# AJH_module_tester-v1_00.net
KiCad netlist of a schematic drawn in EAGLE
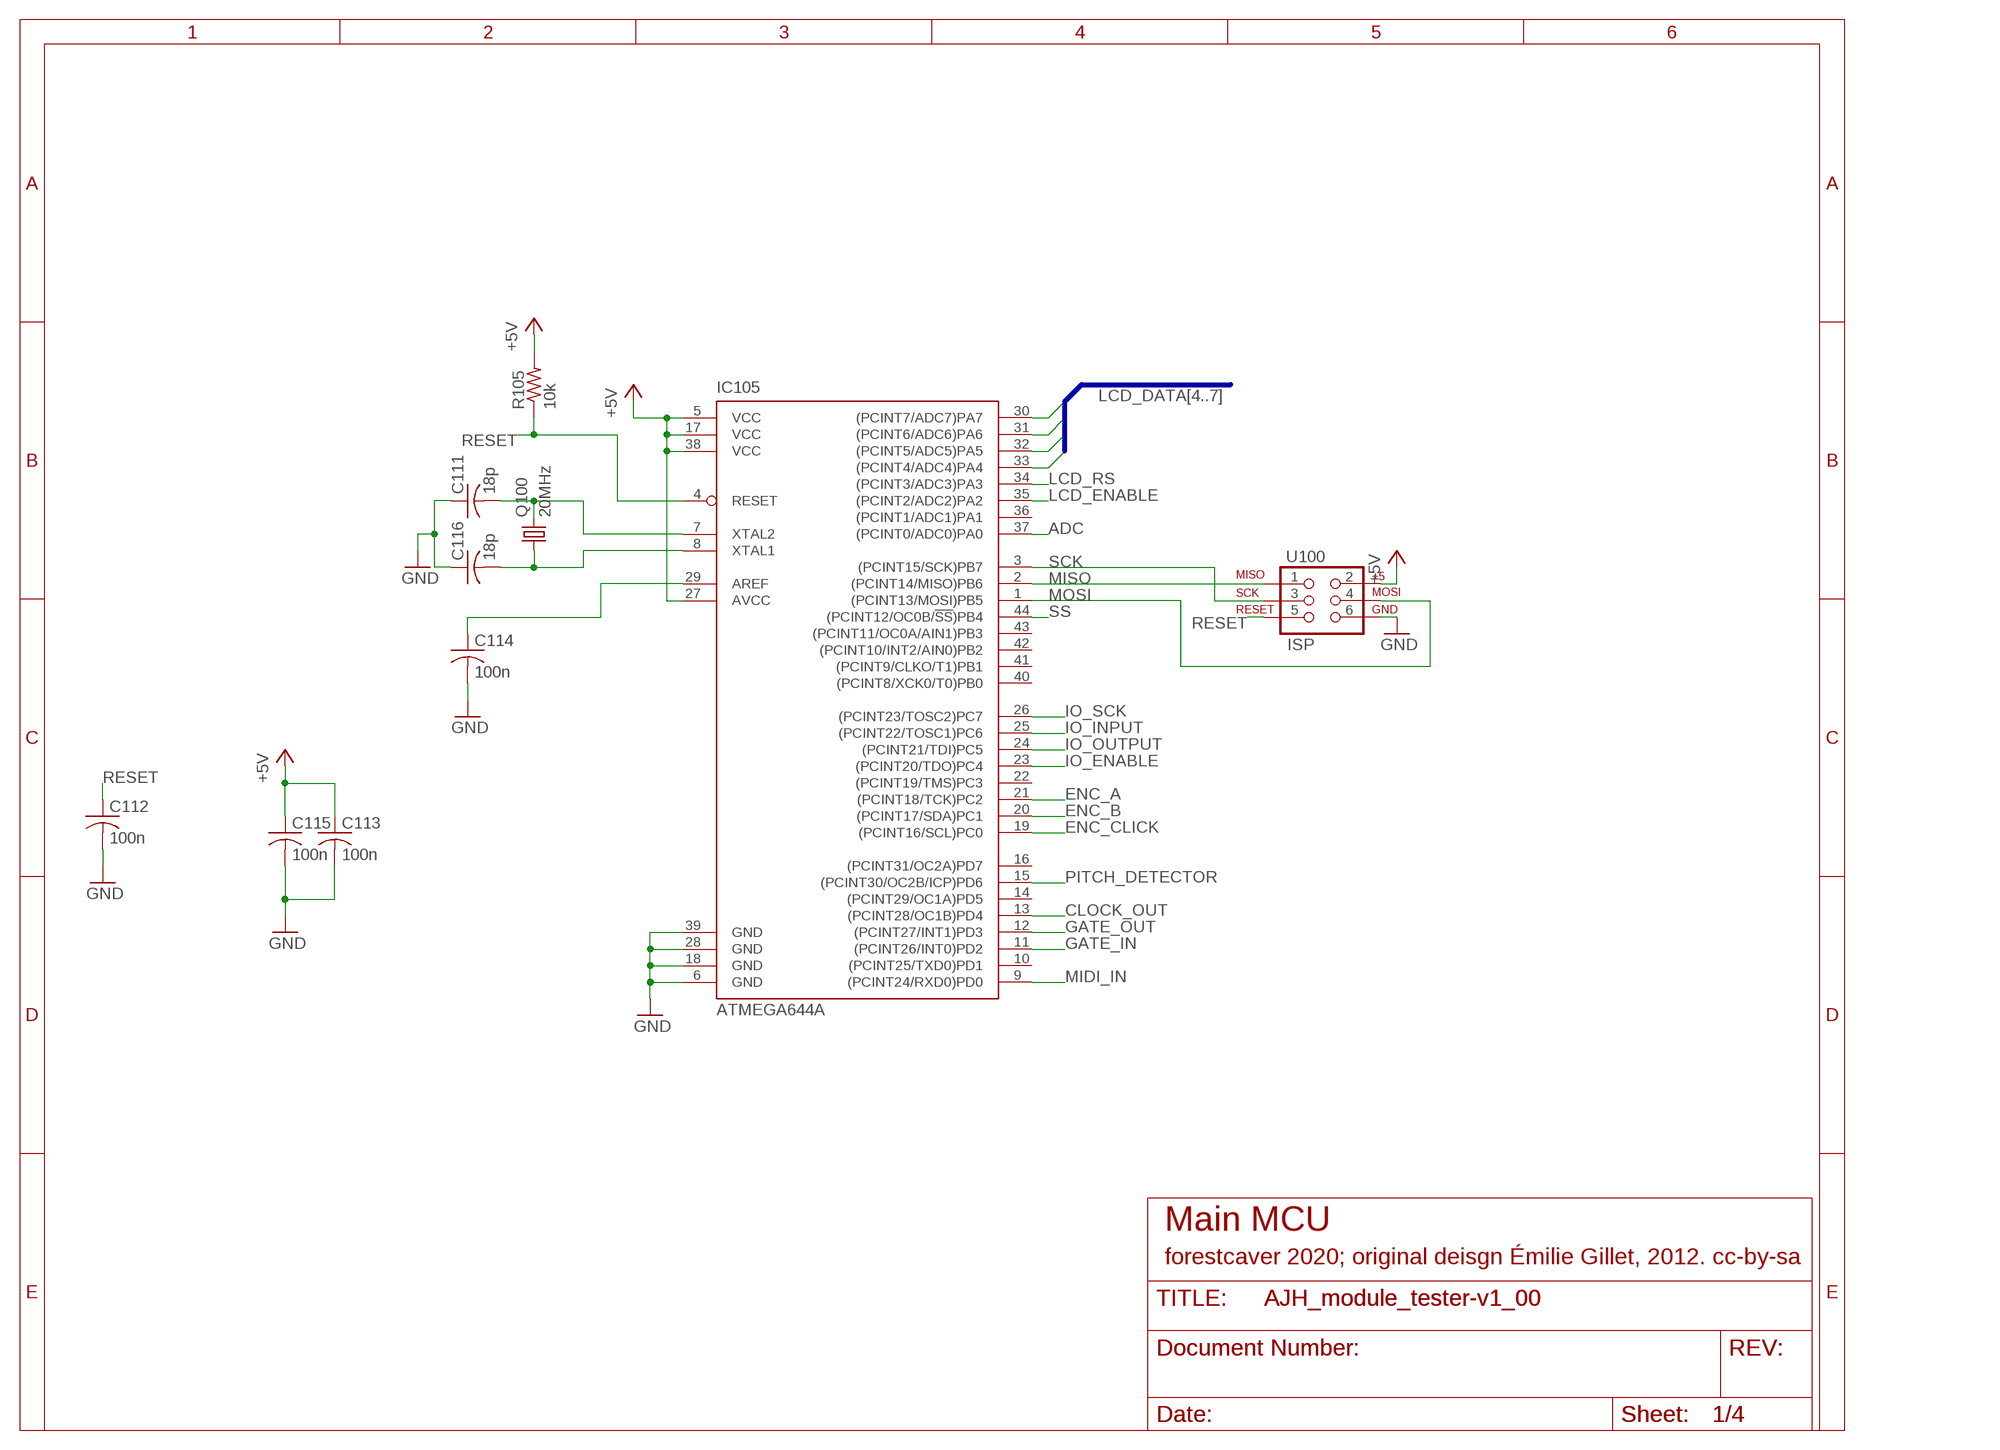
[diagram p0: schematic, sheet 1]
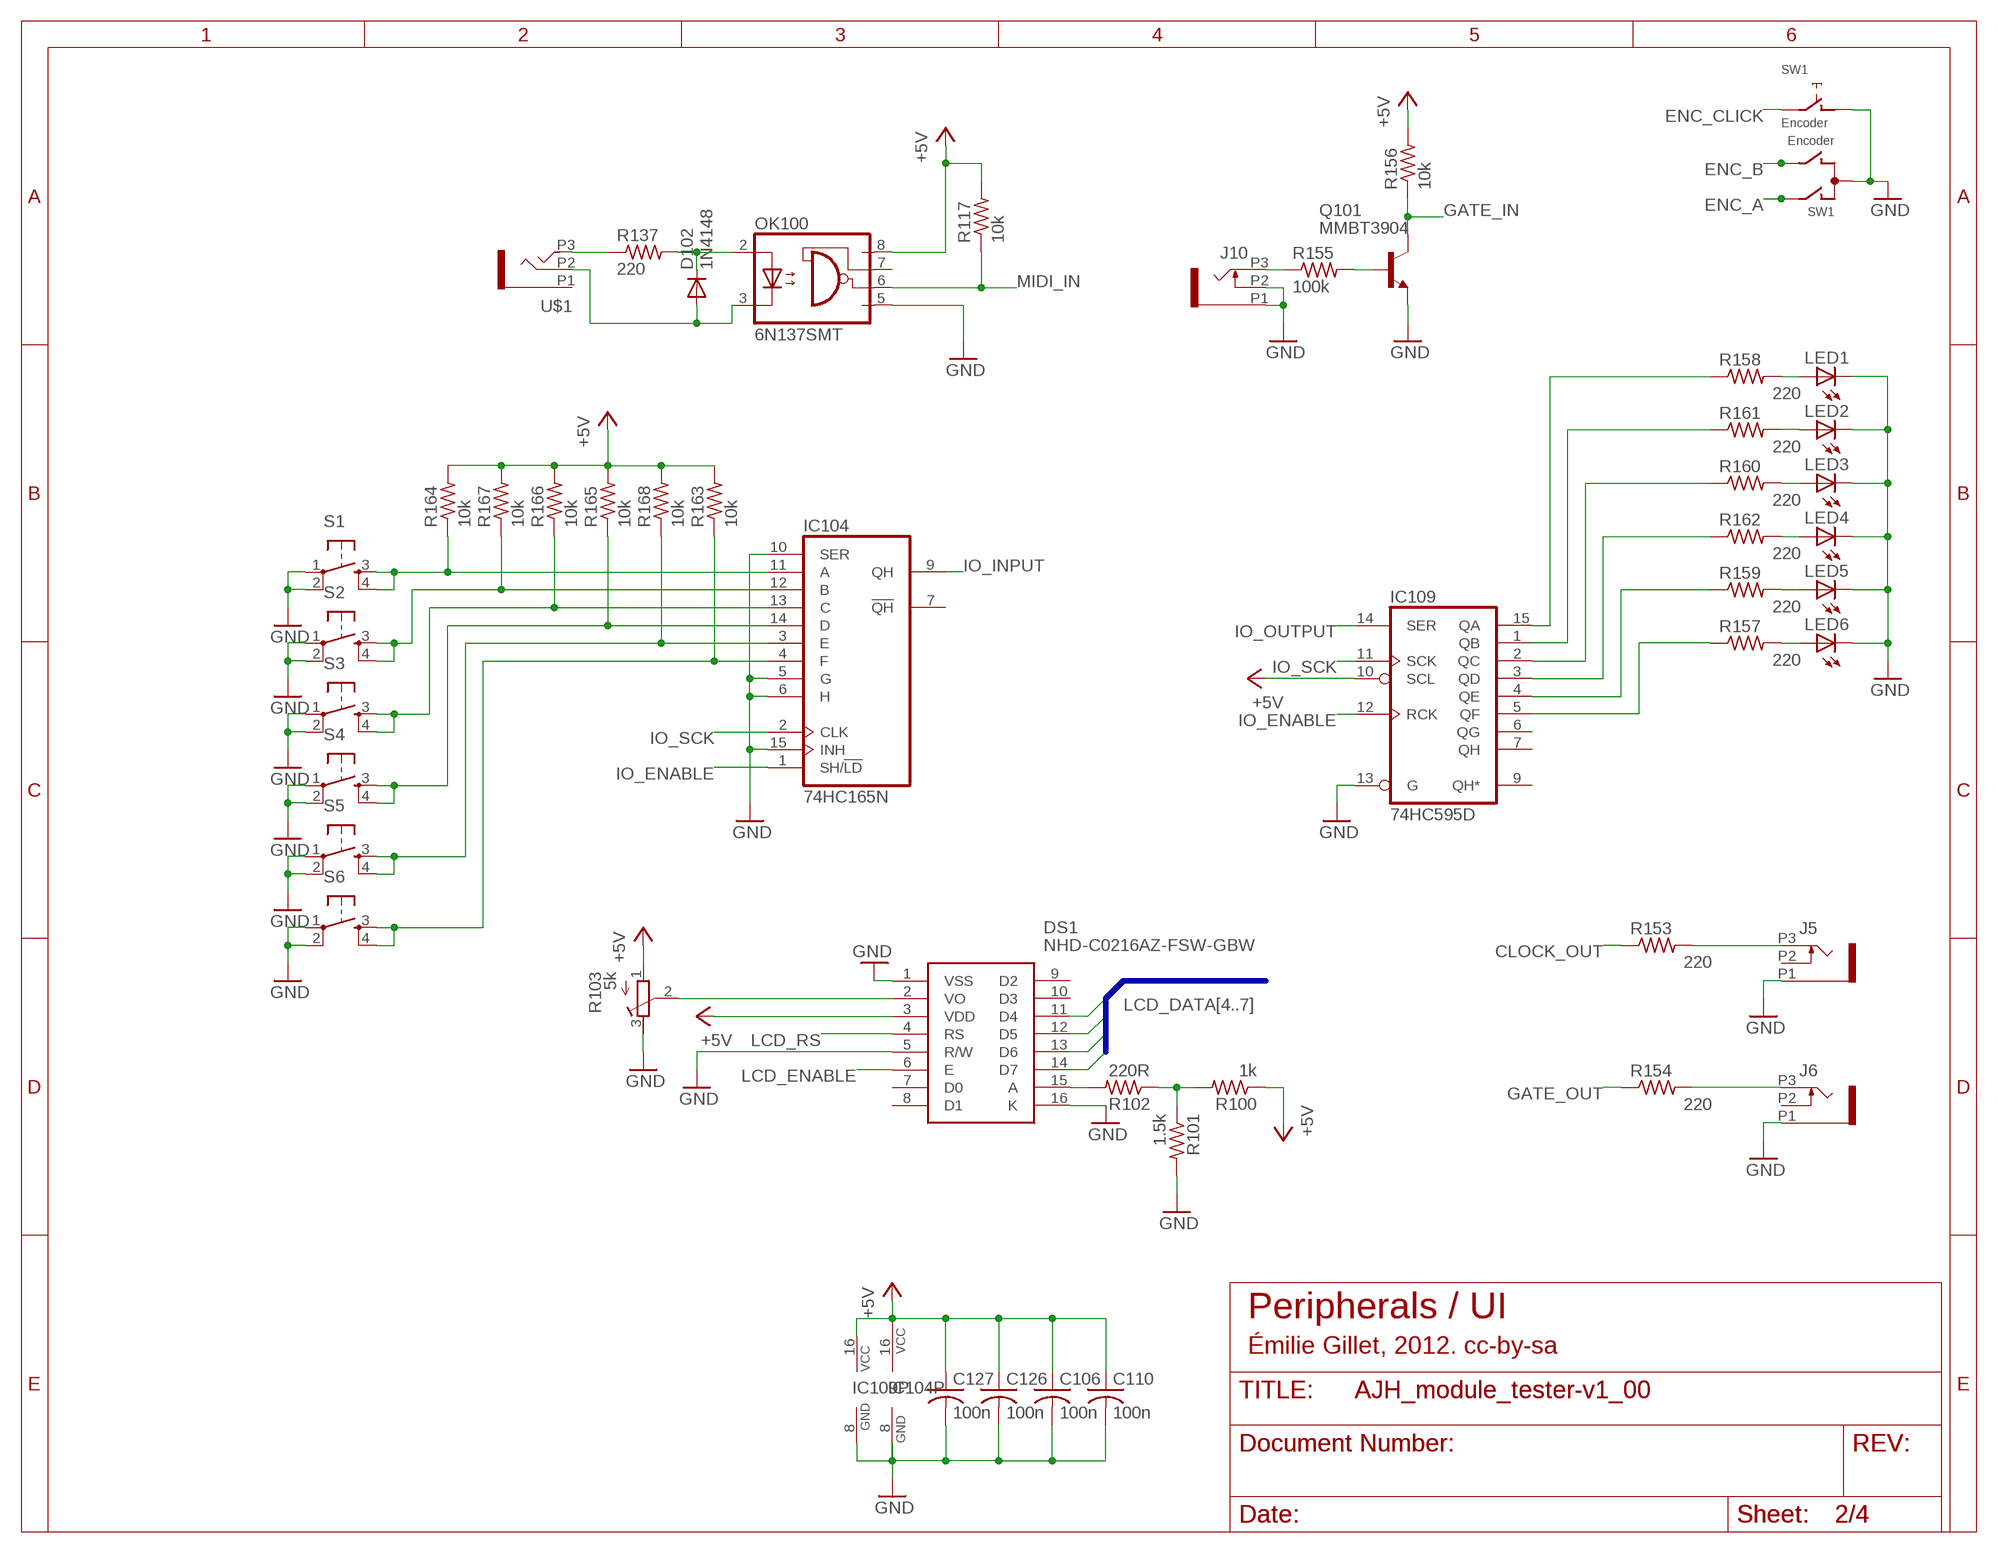
[diagram p1: schematic, sheet 2]
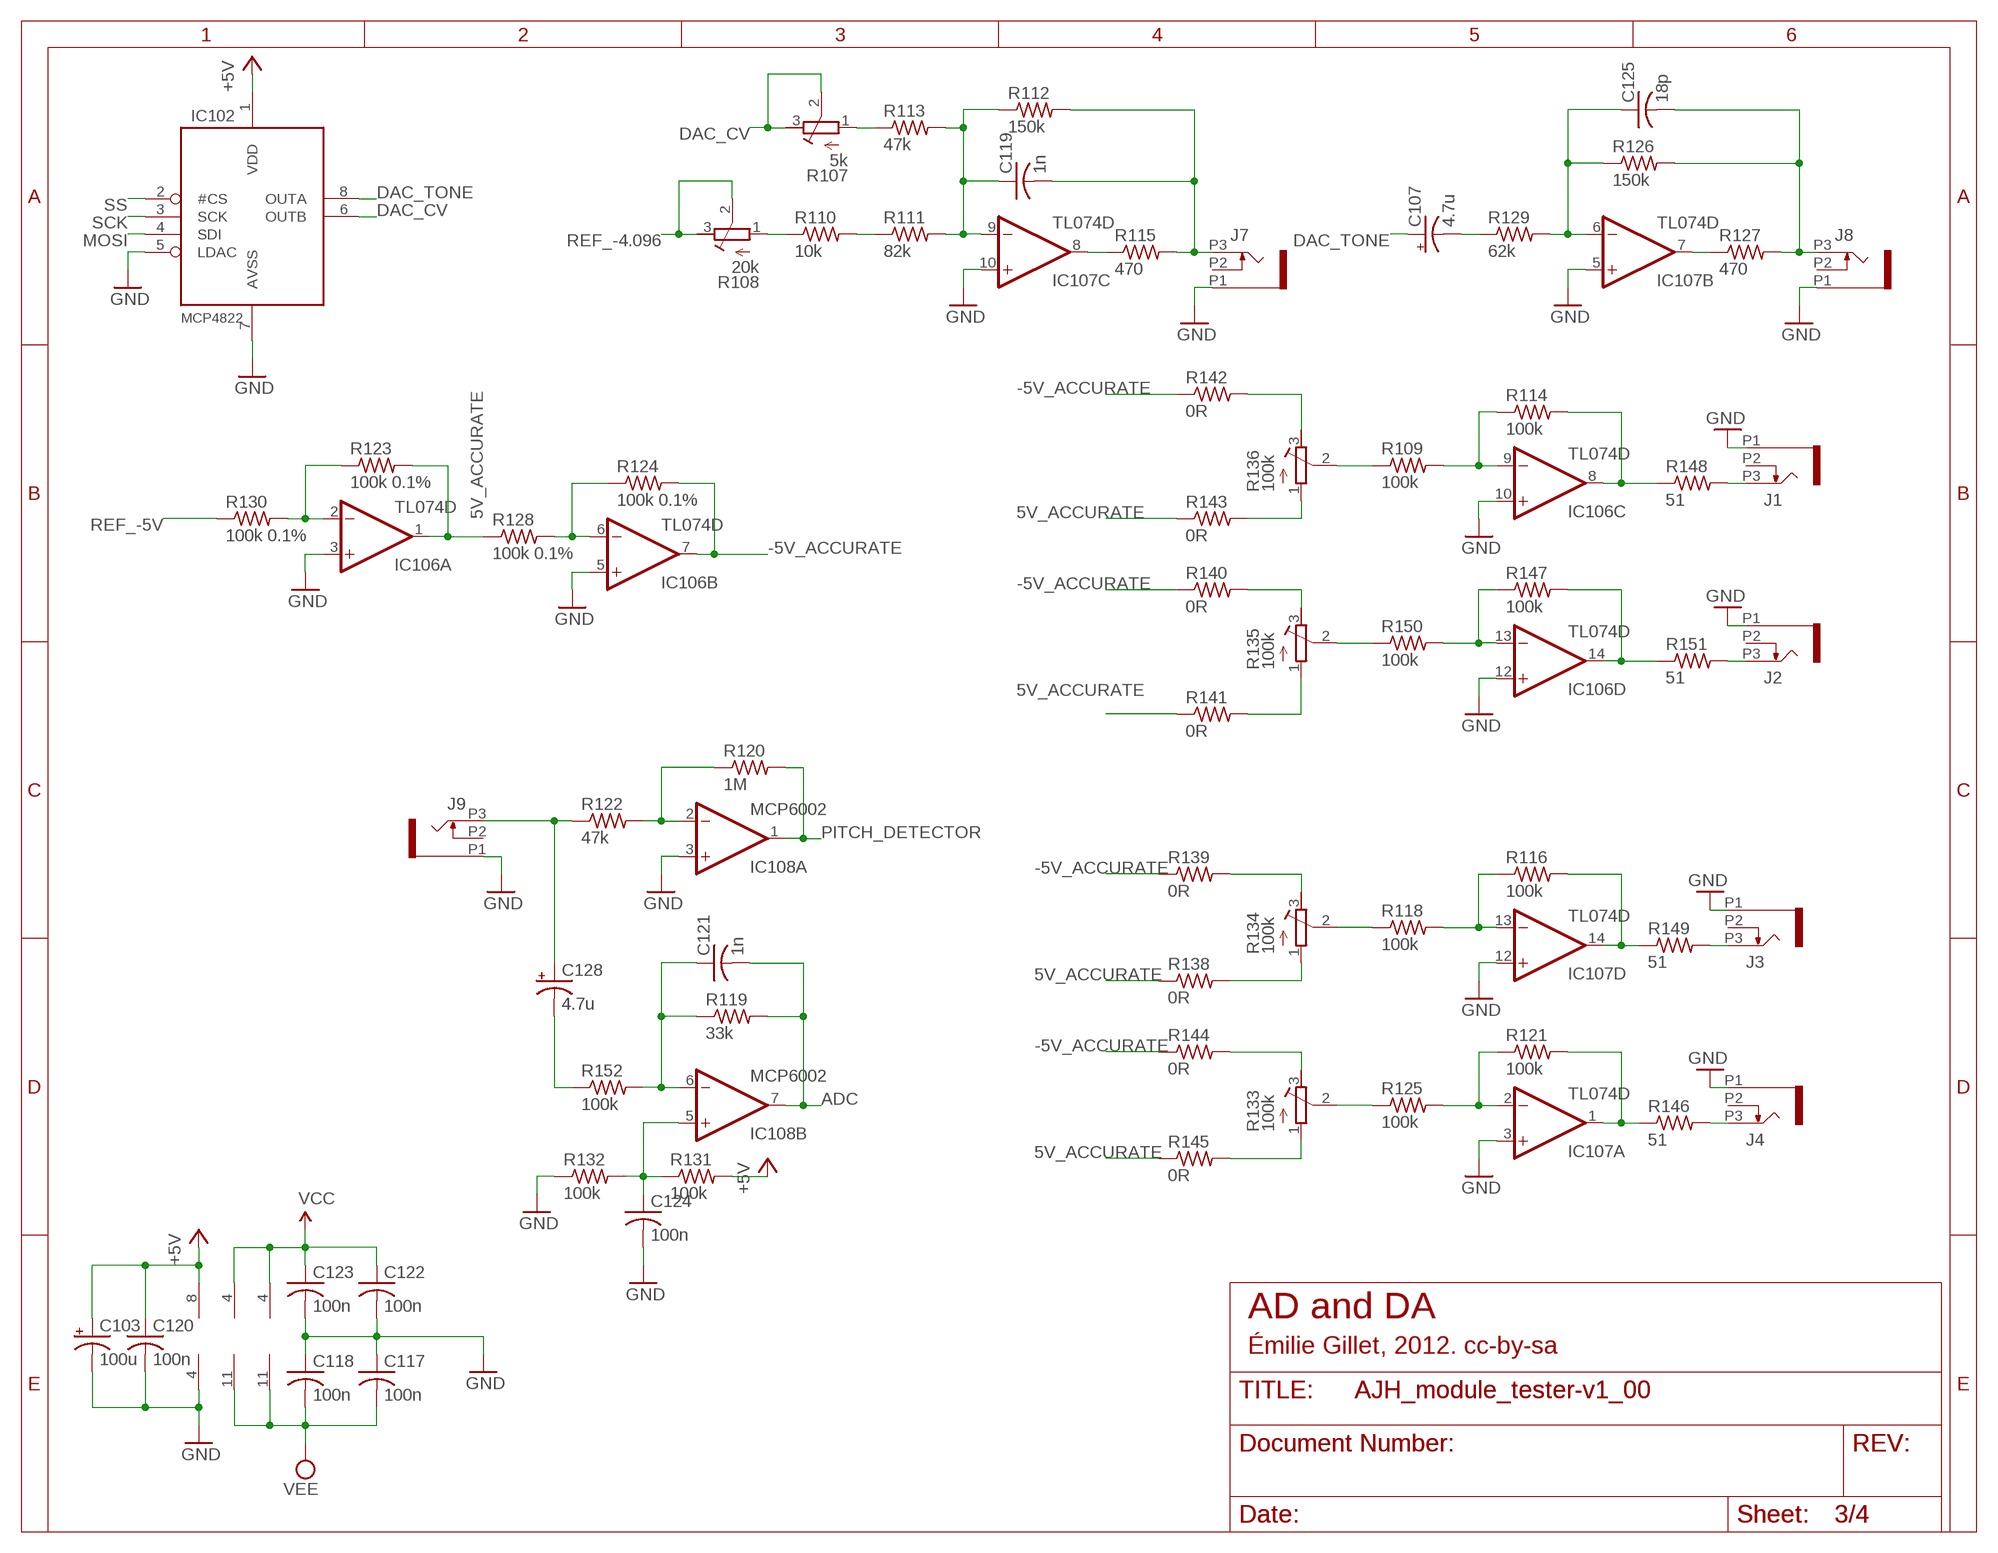
[diagram p2: schematic, sheet 3]
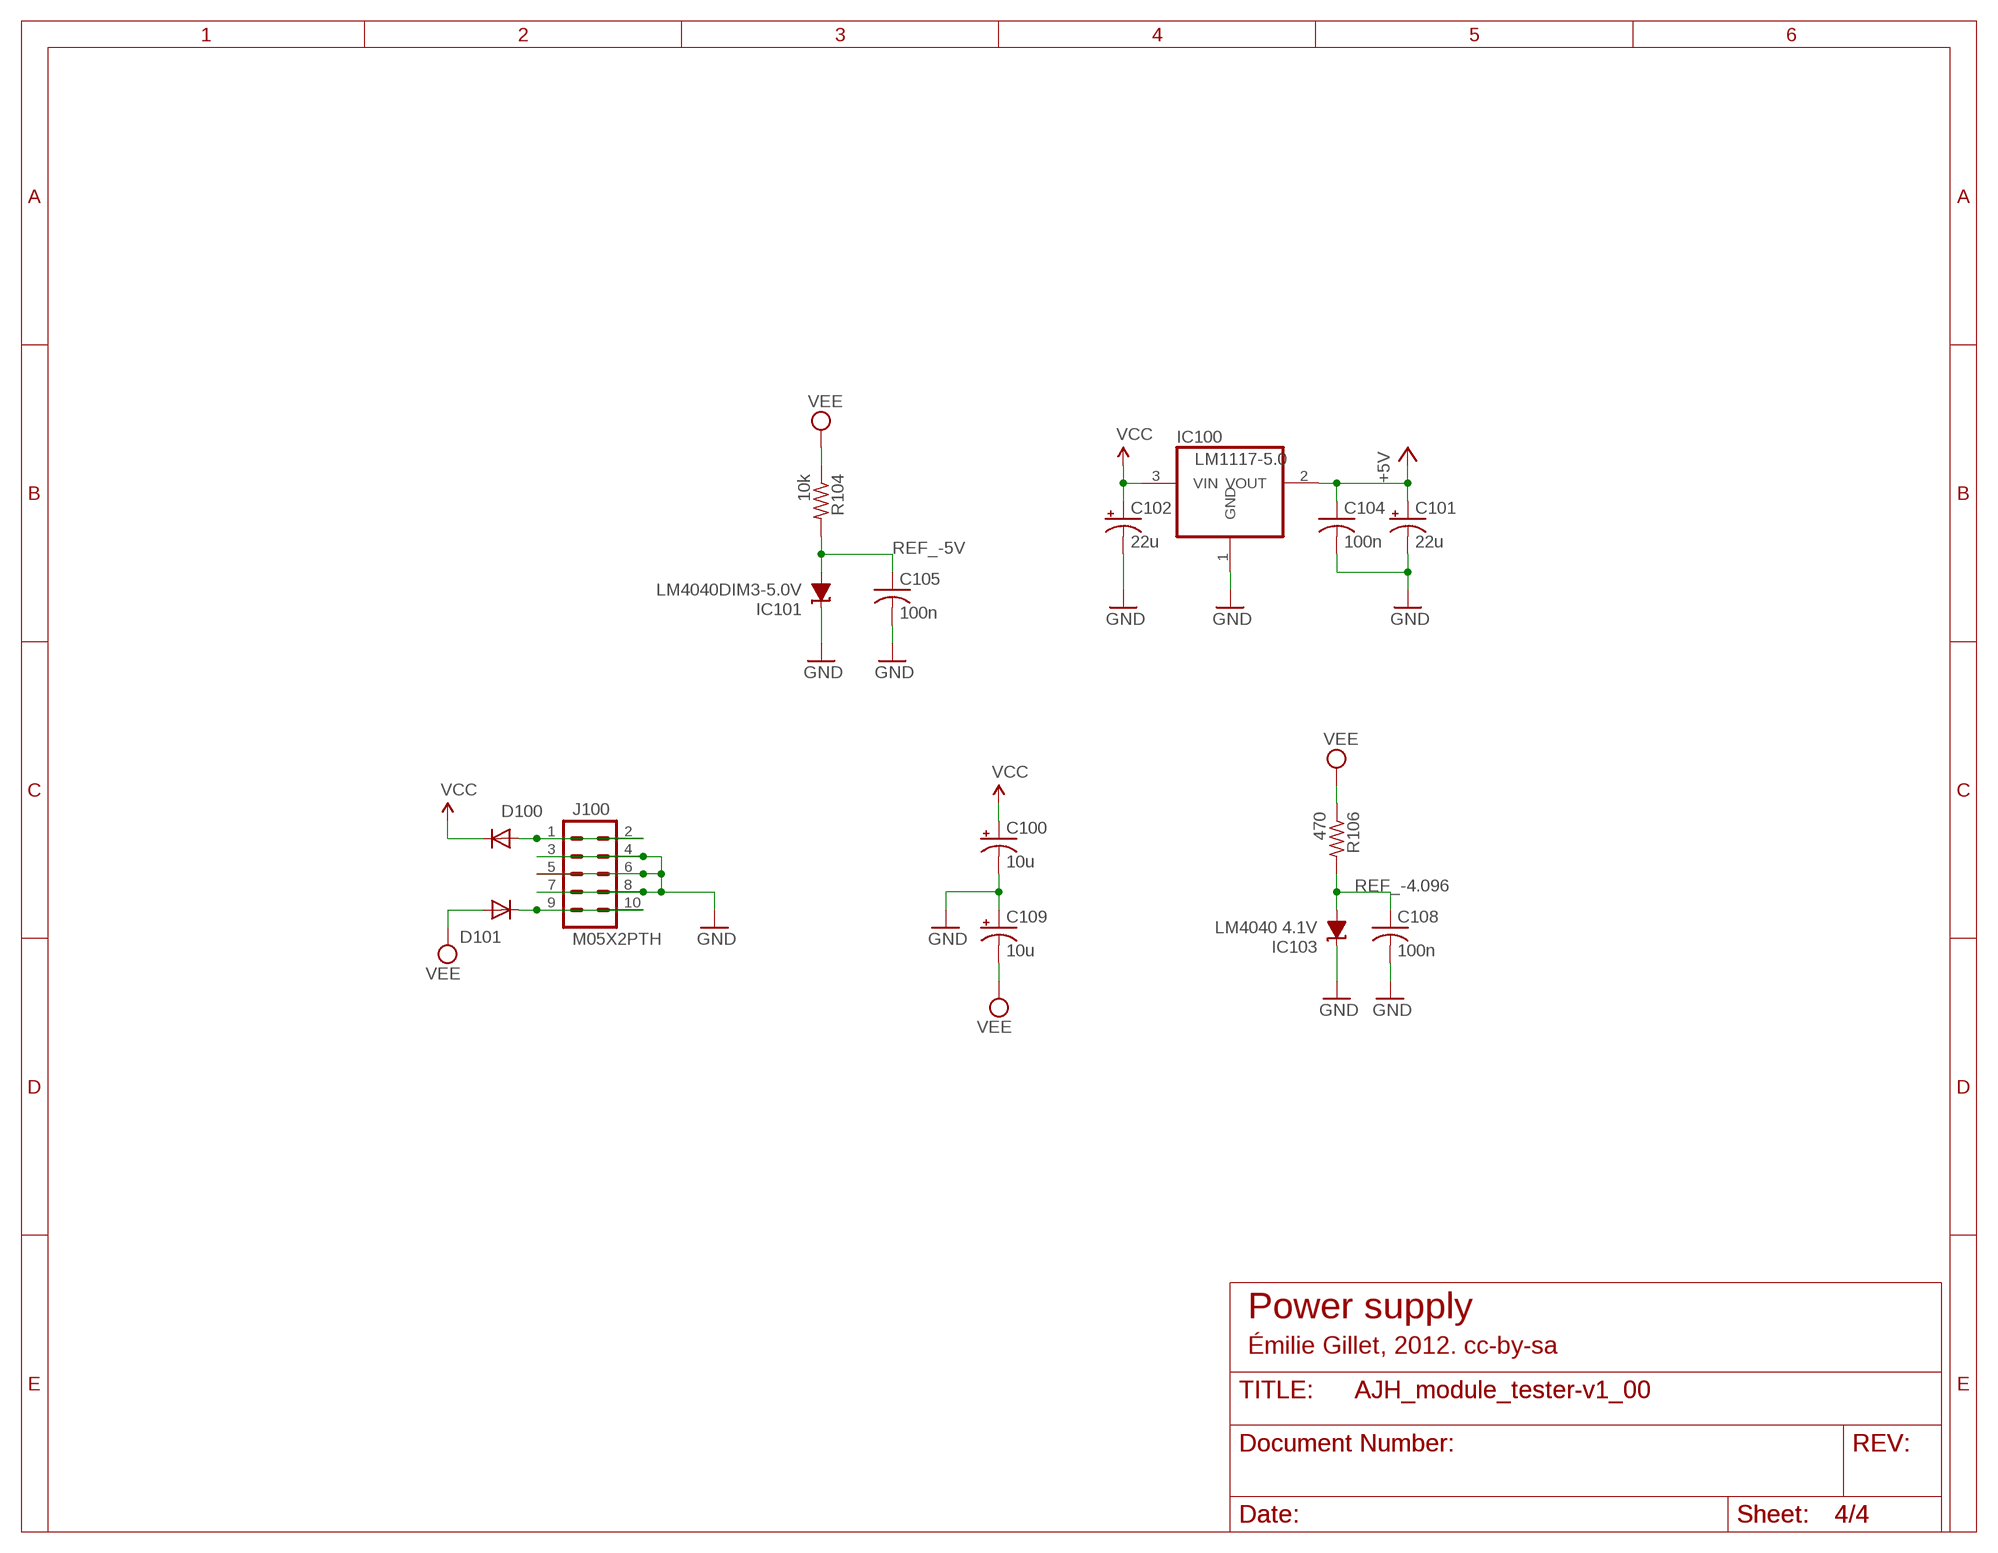
[diagram p3: schematic, sheet 4]

(export (version "E")
  (design (tool "Eeschema 10.0.6"))
  (components
    (comp (ref "C103")
      (value "100u")
      (footprint "eagle-import:PANASONIC_C")
      (libsource (lib "eagle-import") (part "rcl_334_CPOL-USC"))
    )
    (comp (ref "C107")
      (value "4.7u")
      (footprint "eagle-import:PANASONIC_B")
      (libsource (lib "eagle-import") (part "rcl_334_CPOL-USB"))
    )
    (comp (ref "C117")
      (value "100n")
      (footprint "eagle-import:C0603")
      (libsource (lib "eagle-import") (part "C-USC0603"))
    )
    (comp (ref "C118")
      (value "100n")
      (footprint "eagle-import:C0603")
      (libsource (lib "eagle-import") (part "C-USC0603"))
    )
    (comp (ref "C119")
      (value "1n")
      (footprint "eagle-import:C0603")
      (libsource (lib "eagle-import") (part "C-USC0603"))
    )
    (comp (ref "C120")
      (value "100n")
      (footprint "eagle-import:C0603")
      (libsource (lib "eagle-import") (part "C-USC0603"))
    )
    (comp (ref "C121")
      (value "1n")
      (footprint "eagle-import:C0603")
      (libsource (lib "eagle-import") (part "C-USC0603"))
    )
    (comp (ref "C122")
      (value "100n")
      (footprint "eagle-import:C0603")
      (libsource (lib "eagle-import") (part "C-USC0603"))
    )
    (comp (ref "C123")
      (value "100n")
      (footprint "eagle-import:C0603")
      (libsource (lib "eagle-import") (part "C-USC0603"))
    )
    (comp (ref "C124")
      (value "100n")
      (footprint "eagle-import:C0603")
      (libsource (lib "eagle-import") (part "C-USC0603"))
    )
    (comp (ref "C125")
      (value "18p")
      (footprint "eagle-import:C0603")
      (libsource (lib "eagle-import") (part "C-USC0603"))
    )
    (comp (ref "C128")
      (value "4.7u")
      (footprint "eagle-import:PANASONIC_B")
      (libsource (lib "eagle-import") (part "rcl_334_CPOL-USB"))
    )
    (comp (ref "IC102")
      (value "MCP4822SO08")
      (footprint "eagle-import:SO08")
      (libsource (lib "eagle-import") (part "MCP4822SO08"))
    )
    (comp (ref "IC106")
      (value "TL074D")
      (footprint "eagle-import:SO14")
      (libsource (lib "eagle-import") (part "TL074D"))
    )
    (comp (ref "IC107")
      (value "TL074D")
      (footprint "eagle-import:SO14")
      (libsource (lib "eagle-import") (part "TL074D"))
    )
    (comp (ref "IC108")
      (value "MCP6002")
      (footprint "eagle-import:SO08")
      (libsource (lib "eagle-import") (part "TL072D"))
    )
    (comp (ref "J1")
      (value "PJ301_THONKICONN6")
      (footprint "eagle-import:WQP_PJ_301M6")
      (libsource (lib "eagle-import") (part "PJ301_THONKICONN6"))
    )
    (comp (ref "J2")
      (value "PJ301_THONKICONN6")
      (footprint "eagle-import:WQP_PJ_301M6")
      (libsource (lib "eagle-import") (part "PJ301_THONKICONN6"))
    )
    (comp (ref "J3")
      (value "PJ301_THONKICONN6")
      (footprint "eagle-import:WQP_PJ_301M6")
      (libsource (lib "eagle-import") (part "PJ301_THONKICONN6"))
    )
    (comp (ref "J4")
      (value "PJ301_THONKICONN6")
      (footprint "eagle-import:WQP_PJ_301M6")
      (libsource (lib "eagle-import") (part "PJ301_THONKICONN6"))
    )
    (comp (ref "J7")
      (value "PJ301_THONKICONN6")
      (footprint "eagle-import:WQP_PJ_301M6")
      (libsource (lib "eagle-import") (part "PJ301_THONKICONN6"))
    )
    (comp (ref "J8")
      (value "PJ301_THONKICONN6")
      (footprint "eagle-import:WQP_PJ_301M6")
      (libsource (lib "eagle-import") (part "PJ301_THONKICONN6"))
    )
    (comp (ref "J9")
      (value "PJ301_THONKICONN6")
      (footprint "eagle-import:WQP_PJ_301M6")
      (libsource (lib "eagle-import") (part "PJ301_THONKICONN6"))
    )
    (comp (ref "R107")
      (value "5k")
      (footprint "eagle-import:RTRIM3296W")
      (libsource (lib "eagle-import") (part "R-TRIMM3296W"))
    )
    (comp (ref "R108")
      (value "20k")
      (footprint "eagle-import:RTRIM3296W")
      (libsource (lib "eagle-import") (part "R-TRIMM3296W"))
    )
    (comp (ref "R109")
      (value "100k")
      (footprint "eagle-import:R0603")
      (libsource (lib "eagle-import") (part "R-US_R0603"))
    )
    (comp (ref "R110")
      (value "10k")
      (footprint "eagle-import:R0603")
      (libsource (lib "eagle-import") (part "R-US_R0603"))
    )
    (comp (ref "R111")
      (value "82k")
      (footprint "eagle-import:R0603")
      (libsource (lib "eagle-import") (part "R-US_R0603"))
    )
    (comp (ref "R112")
      (value "150k")
      (footprint "eagle-import:R0603")
      (libsource (lib "eagle-import") (part "R-US_R0603"))
    )
    (comp (ref "R113")
      (value "47k")
      (footprint "eagle-import:R0603")
      (libsource (lib "eagle-import") (part "R-US_R0603"))
    )
    (comp (ref "R114")
      (value "100k")
      (footprint "eagle-import:R0603")
      (libsource (lib "eagle-import") (part "R-US_R0603"))
    )
    (comp (ref "R115")
      (value "470")
      (footprint "eagle-import:R0603")
      (libsource (lib "eagle-import") (part "R-US_R0603"))
    )
    (comp (ref "R116")
      (value "100k")
      (footprint "eagle-import:R0603")
      (libsource (lib "eagle-import") (part "R-US_R0603"))
    )
    (comp (ref "R118")
      (value "100k")
      (footprint "eagle-import:R0603")
      (libsource (lib "eagle-import") (part "R-US_R0603"))
    )
    (comp (ref "R119")
      (value "33k")
      (footprint "eagle-import:R0603")
      (libsource (lib "eagle-import") (part "R-US_R0603"))
    )
    (comp (ref "R120")
      (value "1M")
      (footprint "eagle-import:R0603")
      (libsource (lib "eagle-import") (part "R-US_R0603"))
    )
    (comp (ref "R121")
      (value "100k")
      (footprint "eagle-import:R0603")
      (libsource (lib "eagle-import") (part "R-US_R0603"))
    )
    (comp (ref "R122")
      (value "47k")
      (footprint "eagle-import:R0603")
      (libsource (lib "eagle-import") (part "R-US_R0603"))
    )
    (comp (ref "R123")
      (value "100k 0.1%")
      (footprint "eagle-import:R0603")
      (libsource (lib "eagle-import") (part "R-US_R0603"))
    )
    (comp (ref "R124")
      (value "100k 0.1%")
      (footprint "eagle-import:R0603")
      (libsource (lib "eagle-import") (part "R-US_R0603"))
    )
    (comp (ref "R125")
      (value "100k")
      (footprint "eagle-import:R0603")
      (libsource (lib "eagle-import") (part "R-US_R0603"))
    )
    (comp (ref "R126")
      (value "150k")
      (footprint "eagle-import:R0603")
      (libsource (lib "eagle-import") (part "R-US_R0603"))
    )
    (comp (ref "R127")
      (value "470")
      (footprint "eagle-import:R0603")
      (libsource (lib "eagle-import") (part "R-US_R0603"))
    )
    (comp (ref "R128")
      (value "100k 0.1%")
      (footprint "eagle-import:R0603")
      (libsource (lib "eagle-import") (part "R-US_R0603"))
    )
    (comp (ref "R129")
      (value "62k")
      (footprint "eagle-import:R0603")
      (libsource (lib "eagle-import") (part "R-US_R0603"))
    )
    (comp (ref "R130")
      (value "100k 0.1%")
      (footprint "eagle-import:R0603")
      (libsource (lib "eagle-import") (part "R-US_R0603"))
    )
    (comp (ref "R131")
      (value "100k")
      (footprint "eagle-import:R0603")
      (libsource (lib "eagle-import") (part "R-US_R0603"))
    )
    (comp (ref "R132")
      (value "100k")
      (footprint "eagle-import:R0603")
      (libsource (lib "eagle-import") (part "R-US_R0603"))
    )
    (comp (ref "R133")
      (value "100k")
      (footprint "eagle-import:RTRIM3296W")
      (libsource (lib "eagle-import") (part "R-TRIMM3296W"))
    )
    (comp (ref "R134")
      (value "100k")
      (footprint "eagle-import:RTRIM3296W")
      (libsource (lib "eagle-import") (part "R-TRIMM3296W"))
    )
    (comp (ref "R135")
      (value "100k")
      (footprint "eagle-import:RTRIM3296W")
      (libsource (lib "eagle-import") (part "R-TRIMM3296W"))
    )
    (comp (ref "R136")
      (value "100k")
      (footprint "eagle-import:RTRIM3296W")
      (libsource (lib "eagle-import") (part "R-TRIMM3296W"))
    )
    (comp (ref "R138")
      (value "0R")
      (footprint "eagle-import:R0603")
      (libsource (lib "eagle-import") (part "R-US_R0603"))
    )
    (comp (ref "R139")
      (value "0R")
      (footprint "eagle-import:R0603")
      (libsource (lib "eagle-import") (part "R-US_R0603"))
    )
    (comp (ref "R140")
      (value "0R")
      (footprint "eagle-import:R0603")
      (libsource (lib "eagle-import") (part "R-US_R0603"))
    )
    (comp (ref "R141")
      (value "0R")
      (footprint "eagle-import:R0603")
      (libsource (lib "eagle-import") (part "R-US_R0603"))
    )
    (comp (ref "R142")
      (value "0R")
      (footprint "eagle-import:R0603")
      (libsource (lib "eagle-import") (part "R-US_R0603"))
    )
    (comp (ref "R143")
      (value "0R")
      (footprint "eagle-import:R0603")
      (libsource (lib "eagle-import") (part "R-US_R0603"))
    )
    (comp (ref "R144")
      (value "0R")
      (footprint "eagle-import:R0603")
      (libsource (lib "eagle-import") (part "R-US_R0603"))
    )
    (comp (ref "R145")
      (value "0R")
      (footprint "eagle-import:R0603")
      (libsource (lib "eagle-import") (part "R-US_R0603"))
    )
    (comp (ref "R146")
      (value "51")
      (footprint "eagle-import:R0603")
      (libsource (lib "eagle-import") (part "R-US_R0603"))
    )
    (comp (ref "R147")
      (value "100k")
      (footprint "eagle-import:R0603")
      (libsource (lib "eagle-import") (part "R-US_R0603"))
    )
    (comp (ref "R148")
      (value "51")
      (footprint "eagle-import:R0603")
      (libsource (lib "eagle-import") (part "R-US_R0603"))
    )
    (comp (ref "R149")
      (value "51")
      (footprint "eagle-import:R0603")
      (libsource (lib "eagle-import") (part "R-US_R0603"))
    )
    (comp (ref "R150")
      (value "100k")
      (footprint "eagle-import:R0603")
      (libsource (lib "eagle-import") (part "R-US_R0603"))
    )
    (comp (ref "R151")
      (value "51")
      (footprint "eagle-import:R0603")
      (libsource (lib "eagle-import") (part "R-US_R0603"))
    )
    (comp (ref "R152")
      (value "100k")
      (footprint "eagle-import:R0603")
      (libsource (lib "eagle-import") (part "R-US_R0603"))
    )
    (comp (ref "C111")
      (value "18p")
      (footprint "eagle-import:C0603")
      (libsource (lib "eagle-import") (part "C-USC0603"))
    )
    (comp (ref "C112")
      (value "100n")
      (footprint "eagle-import:C0603")
      (libsource (lib "eagle-import") (part "C-USC0603"))
    )
    (comp (ref "C113")
      (value "100n")
      (footprint "eagle-import:C0603")
      (libsource (lib "eagle-import") (part "C-USC0603"))
    )
    (comp (ref "C114")
      (value "100n")
      (footprint "eagle-import:C0603")
      (libsource (lib "eagle-import") (part "C-USC0603"))
    )
    (comp (ref "C115")
      (value "100n")
      (footprint "eagle-import:C0603")
      (libsource (lib "eagle-import") (part "C-USC0603"))
    )
    (comp (ref "C116")
      (value "18p")
      (footprint "eagle-import:C0603")
      (libsource (lib "eagle-import") (part "C-USC0603"))
    )
    (comp (ref "IC105")
      (value "ATMEGA644A")
      (footprint "eagle-import:TQFP44")
      (fields (field (name "MPN") "ATMEGA644PV-10AU"))
      (libsource (lib "eagle-import") (part "ATMEGA644A"))
    )
    (comp (ref "Q100")
      (value "20MHz")
      (footprint "eagle-import:HC49UP")
      (libsource (lib "eagle-import") (part "CRYSTALHC49UP"))
    )
    (comp (ref "R105")
      (value "10k")
      (footprint "eagle-import:R0603")
      (libsource (lib "eagle-import") (part "R-US_R0603"))
    )
    (comp (ref "U100")
      (value "ISP")
      (footprint "eagle-import:2X3")
      (libsource (lib "eagle-import") (part "AVR_SPI_PRG_6PTH"))
    )
    (comp (ref "C106")
      (value "100n")
      (footprint "eagle-import:C0603")
      (libsource (lib "eagle-import") (part "C-USC0603"))
    )
    (comp (ref "C110")
      (value "100n")
      (footprint "eagle-import:C0603")
      (libsource (lib "eagle-import") (part "C-USC0603"))
    )
    (comp (ref "C126")
      (value "100n")
      (footprint "eagle-import:C0603")
      (libsource (lib "eagle-import") (part "C-USC0603"))
    )
    (comp (ref "C127")
      (value "100n")
      (footprint "eagle-import:C0603")
      (libsource (lib "eagle-import") (part "C-USC0603"))
    )
    (comp (ref "D102")
      (value "1N4148")
      (footprint "eagle-import:SOD123")
      (libsource (lib "eagle-import") (part "DIODE-SOD123"))
    )
    (comp (ref "DS1")
      (value "NHD-C0216AZ-FSW-GBW")
      (footprint "eagle-import:NHDC0216AZFSWGBW")
      (fields (field (name "MOUSER_PART_NUMBER") "763-C0216AZ-FSW-GBW"))
      (libsource (lib "eagle-import") (part "NHD-C0216AZ-FSW-GBW"))
    )
    (comp (ref "IC104")
      (value "74HC165N")
      (footprint "eagle-import:SO16")
      (libsource (lib "eagle-import") (part "74165DLS"))
    )
    (comp (ref "IC109")
      (value "74HC595D")
      (footprint "eagle-import:SO16")
      (libsource (lib "eagle-import") (part "74595DHC"))
    )
    (comp (ref "J5")
      (value "PJ301_THONKICONN6")
      (footprint "eagle-import:WQP_PJ_301M6")
      (libsource (lib "eagle-import") (part "PJ301_THONKICONN6"))
    )
    (comp (ref "J6")
      (value "PJ301_THONKICONN6")
      (footprint "eagle-import:WQP_PJ_301M6")
      (libsource (lib "eagle-import") (part "PJ301_THONKICONN6"))
    )
    (comp (ref "J10")
      (value "PJ301_THONKICONN6")
      (footprint "eagle-import:WQP_PJ_301M6")
      (libsource (lib "eagle-import") (part "PJ301_THONKICONN6"))
    )
    (comp (ref "LED1")
      (value "LED3MM")
      (footprint "eagle-import:LED3MM")
      (libsource (lib "eagle-import") (part "LED3MM"))
    )
    (comp (ref "LED2")
      (value "LED3MM")
      (footprint "eagle-import:LED3MM")
      (libsource (lib "eagle-import") (part "LED3MM"))
    )
    (comp (ref "LED3")
      (value "LED3MM")
      (footprint "eagle-import:LED3MM")
      (libsource (lib "eagle-import") (part "LED3MM"))
    )
    (comp (ref "LED4")
      (value "LED3MM")
      (footprint "eagle-import:LED3MM")
      (libsource (lib "eagle-import") (part "LED3MM"))
    )
    (comp (ref "LED5")
      (value "LED3MM")
      (footprint "eagle-import:LED3MM")
      (libsource (lib "eagle-import") (part "LED3MM"))
    )
    (comp (ref "LED6")
      (value "LED3MM")
      (footprint "eagle-import:LED3MM")
      (libsource (lib "eagle-import") (part "LED3MM"))
    )
    (comp (ref "OK100")
      (value "6N137SMT")
      (footprint "eagle-import:DIL8-SMD")
      (libsource (lib "eagle-import") (part "6N137SMT"))
    )
    (comp (ref "Q101")
      (value "MMBT3904")
      (footprint "eagle-import:SOT23-BEC")
      (libsource (lib "eagle-import") (part "-NPN-SOT23-BECMMBT3904LT1"))
    )
    (comp (ref "R100")
      (value "1k")
      (footprint "eagle-import:R0603")
      (libsource (lib "eagle-import") (part "R-US_R0603"))
    )
    (comp (ref "R101")
      (value "1.5k")
      (footprint "eagle-import:R0603")
      (libsource (lib "eagle-import") (part "R-US_R0603"))
    )
    (comp (ref "R102")
      (value "220R")
      (footprint "eagle-import:R0603")
      (libsource (lib "eagle-import") (part "R-US_R0603"))
    )
    (comp (ref "R103")
      (value "5k")
      (footprint "eagle-import:RTRIM3339P")
      (libsource (lib "eagle-import") (part "R-TRIMM3339P"))
    )
    (comp (ref "R117")
      (value "10k")
      (footprint "eagle-import:R0603")
      (libsource (lib "eagle-import") (part "R-US_R0603"))
    )
    (comp (ref "R137")
      (value "220")
      (footprint "eagle-import:R0603")
      (libsource (lib "eagle-import") (part "R-US_R0603"))
    )
    (comp (ref "R153")
      (value "220")
      (footprint "eagle-import:R0603")
      (libsource (lib "eagle-import") (part "R-US_R0603"))
    )
    (comp (ref "R154")
      (value "220")
      (footprint "eagle-import:R0603")
      (libsource (lib "eagle-import") (part "R-US_R0603"))
    )
    (comp (ref "R155")
      (value "100k")
      (footprint "eagle-import:R0603")
      (libsource (lib "eagle-import") (part "R-US_R0603"))
    )
    (comp (ref "R156")
      (value "10k")
      (footprint "eagle-import:R0603")
      (libsource (lib "eagle-import") (part "R-US_R0603"))
    )
    (comp (ref "R157")
      (value "220")
      (footprint "eagle-import:R0603")
      (libsource (lib "eagle-import") (part "R-US_R0603"))
    )
    (comp (ref "R158")
      (value "220")
      (footprint "eagle-import:R0603")
      (libsource (lib "eagle-import") (part "R-US_R0603"))
    )
    (comp (ref "R159")
      (value "220")
      (footprint "eagle-import:R0603")
      (libsource (lib "eagle-import") (part "R-US_R0603"))
    )
    (comp (ref "R160")
      (value "220")
      (footprint "eagle-import:R0603")
      (libsource (lib "eagle-import") (part "R-US_R0603"))
    )
    (comp (ref "R161")
      (value "220")
      (footprint "eagle-import:R0603")
      (libsource (lib "eagle-import") (part "R-US_R0603"))
    )
    (comp (ref "R162")
      (value "220")
      (footprint "eagle-import:R0603")
      (libsource (lib "eagle-import") (part "R-US_R0603"))
    )
    (comp (ref "R163")
      (value "10k")
      (footprint "eagle-import:R0603")
      (libsource (lib "eagle-import") (part "R-US_R0603"))
    )
    (comp (ref "R164")
      (value "10k")
      (footprint "eagle-import:R0603")
      (libsource (lib "eagle-import") (part "R-US_R0603"))
    )
    (comp (ref "R165")
      (value "10k")
      (footprint "eagle-import:R0603")
      (libsource (lib "eagle-import") (part "R-US_R0603"))
    )
    (comp (ref "R166")
      (value "10k")
      (footprint "eagle-import:R0603")
      (libsource (lib "eagle-import") (part "R-US_R0603"))
    )
    (comp (ref "R167")
      (value "10k")
      (footprint "eagle-import:R0603")
      (libsource (lib "eagle-import") (part "R-US_R0603"))
    )
    (comp (ref "R168")
      (value "10k")
      (footprint "eagle-import:R0603")
      (libsource (lib "eagle-import") (part "R-US_R0603"))
    )
    (comp (ref "S1")
      (value "TAC_SWITCHPTH")
      (footprint "eagle-import:TACTILE-PTH")
      (libsource (lib "eagle-import") (part "TAC_SWITCHPTH"))
    )
    (comp (ref "S2")
      (value "TAC_SWITCHPTH")
      (footprint "eagle-import:TACTILE-PTH")
      (libsource (lib "eagle-import") (part "TAC_SWITCHPTH"))
    )
    (comp (ref "S3")
      (value "TAC_SWITCHPTH")
      (footprint "eagle-import:TACTILE-PTH")
      (libsource (lib "eagle-import") (part "TAC_SWITCHPTH"))
    )
    (comp (ref "S4")
      (value "TAC_SWITCHPTH")
      (footprint "eagle-import:TACTILE-PTH")
      (libsource (lib "eagle-import") (part "TAC_SWITCHPTH"))
    )
    (comp (ref "S5")
      (value "TAC_SWITCHPTH")
      (footprint "eagle-import:TACTILE-PTH")
      (libsource (lib "eagle-import") (part "TAC_SWITCHPTH"))
    )
    (comp (ref "S6")
      (value "TAC_SWITCHPTH")
      (footprint "eagle-import:TACTILE-PTH")
      (libsource (lib "eagle-import") (part "TAC_SWITCHPTH"))
    )
    (comp (ref "SW1")
      (value "Encoder")
      (footprint "eagle-import:ALPS_EC12E_SW")
      (libsource (lib "eagle-import") (part "EC12E_SW"))
    )
    (comp (ref "U$1")
      (value "PJ366ST")
      (footprint "eagle-import:WQP_PJ_301M8")
      (libsource (lib "eagle-import") (part "PJ366ST"))
    )
    (comp (ref "C100")
      (value "10u")
      (footprint "eagle-import:PANASONIC_B")
      (libsource (lib "eagle-import") (part "rcl_334_CPOL-USB"))
    )
    (comp (ref "C101")
      (value "22u")
      (footprint "eagle-import:PANASONIC_C")
      (libsource (lib "eagle-import") (part "CPOL-USC"))
    )
    (comp (ref "C102")
      (value "22u")
      (footprint "eagle-import:PANASONIC_C")
      (libsource (lib "eagle-import") (part "CPOL-USC"))
    )
    (comp (ref "C104")
      (value "100n")
      (footprint "eagle-import:C0603")
      (libsource (lib "eagle-import") (part "C-USC0603"))
    )
    (comp (ref "C105")
      (value "100n")
      (footprint "eagle-import:C0603")
      (libsource (lib "eagle-import") (part "C-USC0603"))
    )
    (comp (ref "C108")
      (value "100n")
      (footprint "eagle-import:C0603")
      (libsource (lib "eagle-import") (part "C-USC0603"))
    )
    (comp (ref "C109")
      (value "10u")
      (footprint "eagle-import:PANASONIC_B")
      (libsource (lib "eagle-import") (part "rcl_334_CPOL-USB"))
    )
    (comp (ref "D100")
      (value "1N5819HW")
      (footprint "eagle-import:SOD123")
      (libsource (lib "eagle-import") (part "DIODE-SOD123"))
    )
    (comp (ref "D101")
      (value "1N5819HW")
      (footprint "eagle-import:SOD123")
      (libsource (lib "eagle-import") (part "DIODE-SOD123"))
    )
    (comp (ref "IC100")
      (value "LM1117-5.0")
      (footprint "eagle-import:SOT223")
      (libsource (lib "eagle-import") (part "REG1117"))
    )
    (comp (ref "IC101")
      (value "LM4040DIM3-5.0V")
      (footprint "eagle-import:DBZ_R-PDSO-G3")
      (libsource (lib "eagle-import") (part "LM4041DBZC12"))
    )
    (comp (ref "IC103")
      (value "LM4040 4.1V")
      (footprint "eagle-import:DBZ_R-PDSO-G3")
      (libsource (lib "eagle-import") (part "LM4041DBZC12"))
    )
    (comp (ref "J100")
      (value "M05X2PTH")
      (footprint "eagle-import:AVR_ICSP")
      (libsource (lib "eagle-import") (part "M05X2PTH"))
    )
    (comp (ref "R104")
      (value "10k")
      (footprint "eagle-import:R0603")
      (libsource (lib "eagle-import") (part "resistor_R-US_R0603"))
    )
    (comp (ref "R106")
      (value "470")
      (footprint "eagle-import:R0603")
      (libsource (lib "eagle-import") (part "resistor_R-US_R0603"))
    )
  )
  (nets
    (net (code "1") (name "+5V") (class "Default")
      (node (ref "C101") (pin "+") (pinfunction "+_+") (pintype "passive"))
      (node (ref "C103") (pin "+") (pinfunction "+_+") (pintype "passive"))
      (node (ref "C104") (pin "1") (pinfunction "1_1") (pintype "passive"))
      (node (ref "C106") (pin "1") (pinfunction "1_1") (pintype "passive"))
      (node (ref "C110") (pin "1") (pinfunction "1_1") (pintype "passive"))
      (node (ref "C113") (pin "1") (pinfunction "1_1") (pintype "passive"))
      (node (ref "C115") (pin "1") (pinfunction "1_1") (pintype "passive"))
      (node (ref "C120") (pin "1") (pinfunction "1_1") (pintype "passive"))
      (node (ref "C126") (pin "1") (pinfunction "1_1") (pintype "passive"))
      (node (ref "C127") (pin "1") (pinfunction "1_1") (pintype "passive"))
      (node (ref "DS1") (pin "3") (pinfunction "VDD_3") (pintype "bidirectional"))
      (node (ref "IC100") (pin "2") (pinfunction "VOUT_2") (pintype "output"))
      (node (ref "IC102") (pin "1") (pinfunction "VDD_1") (pintype "power_in"))
      (node (ref "IC104") (pin "16") (pinfunction "VCC_16") (pintype "power_in"))
      (node (ref "IC105") (pin "17") (pinfunction "VCC_17") (pintype "power_in"))
      (node (ref "IC105") (pin "27") (pinfunction "AVCC_27") (pintype "power_in"))
      (node (ref "IC105") (pin "38") (pinfunction "VCC_38") (pintype "power_in"))
      (node (ref "IC105") (pin "5") (pinfunction "VCC_5") (pintype "power_in"))
      (node (ref "IC108") (pin "8") (pinfunction "V+_8") (pintype "power_in"))
      (node (ref "IC109") (pin "10") (pinfunction "SCL_10") (pintype "input"))
      (node (ref "IC109") (pin "16") (pinfunction "VCC_16") (pintype "power_in"))
      (node (ref "OK100") (pin "8") (pinfunction "VCC_8") (pintype "passive"))
      (node (ref "R100") (pin "1") (pinfunction "1_1") (pintype "passive"))
      (node (ref "R103") (pin "1") (pinfunction "E_1") (pintype "passive"))
      (node (ref "R105") (pin "2") (pinfunction "2_2") (pintype "passive"))
      (node (ref "R117") (pin "2") (pinfunction "2_2") (pintype "passive"))
      (node (ref "R131") (pin "2") (pinfunction "2_2") (pintype "passive"))
      (node (ref "R156") (pin "2") (pinfunction "2_2") (pintype "passive"))
      (node (ref "R163") (pin "2") (pinfunction "2_2") (pintype "passive"))
      (node (ref "R164") (pin "2") (pinfunction "2_2") (pintype "passive"))
      (node (ref "R165") (pin "2") (pinfunction "2_2") (pintype "passive"))
      (node (ref "R166") (pin "2") (pinfunction "2_2") (pintype "passive"))
      (node (ref "R167") (pin "2") (pinfunction "2_2") (pintype "passive"))
      (node (ref "R168") (pin "2") (pinfunction "2_2") (pintype "passive"))
      (node (ref "U100") (pin "2") (pinfunction "2_2") (pintype "passive"))
    )
    (net (code "2") (name "-5V_ACCURATE") (class "Default")
      (node (ref "IC106") (pin "7") (pinfunction "OUT_7") (pintype "output"))
      (node (ref "R124") (pin "2") (pinfunction "2_2") (pintype "passive"))
      (node (ref "R139") (pin "1") (pinfunction "1_1") (pintype "passive"))
      (node (ref "R140") (pin "1") (pinfunction "1_1") (pintype "passive"))
      (node (ref "R142") (pin "1") (pinfunction "1_1") (pintype "passive"))
      (node (ref "R144") (pin "1") (pinfunction "1_1") (pintype "passive"))
    )
    (net (code "5") (name "5V_ACCURATE") (class "Default")
      (node (ref "IC106") (pin "1") (pinfunction "OUT_1") (pintype "output"))
      (node (ref "R123") (pin "2") (pinfunction "2_2") (pintype "passive"))
      (node (ref "R128") (pin "1") (pinfunction "1_1") (pintype "passive"))
      (node (ref "R138") (pin "1") (pinfunction "1_1") (pintype "passive"))
      (node (ref "R141") (pin "1") (pinfunction "1_1") (pintype "passive"))
      (node (ref "R143") (pin "1") (pinfunction "1_1") (pintype "passive"))
      (node (ref "R145") (pin "1") (pinfunction "1_1") (pintype "passive"))
    )
    (net (code "6") (name "ADC") (class "Default")
      (node (ref "C121") (pin "2") (pinfunction "2_2") (pintype "passive"))
      (node (ref "IC105") (pin "37") (pinfunction "(PCINT0/ADC0)PA0_37") (pintype "bidirectional"))
      (node (ref "IC108") (pin "7") (pinfunction "OUT_7") (pintype "output"))
      (node (ref "R119") (pin "2") (pinfunction "2_2") (pintype "passive"))
    )
    (net (code "7") (name "CLOCK_OUT") (class "Default")
      (node (ref "IC105") (pin "13") (pinfunction "(PCINT28/OC1B)PD4_13") (pintype "bidirectional"))
      (node (ref "R153") (pin "1") (pinfunction "1_1") (pintype "passive"))
    )
    (net (code "8") (name "DAC_CV") (class "Default")
      (node (ref "IC102") (pin "6") (pinfunction "OUTB_6") (pintype "output"))
      (node (ref "R107") (pin "2") (pinfunction "S_2") (pintype "passive"))
      (node (ref "R107") (pin "3") (pinfunction "A_3") (pintype "passive"))
    )
    (net (code "9") (name "DAC_TONE") (class "Default")
      (node (ref "C107") (pin "+") (pinfunction "+_+") (pintype "passive"))
      (node (ref "IC102") (pin "8") (pinfunction "OUTA_8") (pintype "output"))
    )
    (net (code "10") (name "ENC_A") (class "Default")
      (node (ref "IC105") (pin "21") (pinfunction "(PCINT18/TCK)PC2_21") (pintype "output"))
      (node (ref "SW1") (pin "A") (pinfunction "A_A") (pintype "passive"))
    )
    (net (code "11") (name "ENC_B") (class "Default")
      (node (ref "IC105") (pin "20") (pinfunction "(PCINT17/SDA)PC1_20") (pintype "output"))
      (node (ref "SW1") (pin "B") (pinfunction "B_B") (pintype "passive"))
    )
    (net (code "12") (name "ENC_CLICK") (class "Default")
      (node (ref "IC105") (pin "19") (pinfunction "(PCINT16/SCL)PC0_19") (pintype "output"))
      (node (ref "SW1") (pin "E") (pinfunction "2_E") (pintype "passive"))
    )
    (net (code "13") (name "GATE_IN") (class "Default")
      (node (ref "IC105") (pin "11") (pinfunction "(PCINT26/INT0)PD2_11") (pintype "bidirectional"))
      (node (ref "Q101") (pin "C") (pinfunction "C_C") (pintype "passive"))
      (node (ref "R156") (pin "1") (pinfunction "1_1") (pintype "passive"))
    )
    (net (code "14") (name "GATE_OUT") (class "Default")
      (node (ref "IC105") (pin "12") (pinfunction "(PCINT27/INT1)PD3_12") (pintype "bidirectional"))
      (node (ref "R154") (pin "1") (pinfunction "1_1") (pintype "passive"))
    )
    (net (code "15") (name "GND") (class "Default")
      (node (ref "C100") (pin "-") (pinfunction "-_-") (pintype "passive"))
      (node (ref "C101") (pin "-") (pinfunction "-_-") (pintype "passive"))
      (node (ref "C102") (pin "-") (pinfunction "-_-") (pintype "passive"))
      (node (ref "C103") (pin "-") (pinfunction "-_-") (pintype "passive"))
      (node (ref "C104") (pin "2") (pinfunction "2_2") (pintype "passive"))
      (node (ref "C105") (pin "2") (pinfunction "2_2") (pintype "passive"))
      (node (ref "C106") (pin "2") (pinfunction "2_2") (pintype "passive"))
      (node (ref "C108") (pin "2") (pinfunction "2_2") (pintype "passive"))
      (node (ref "C109") (pin "+") (pinfunction "+_+") (pintype "passive"))
      (node (ref "C110") (pin "2") (pinfunction "2_2") (pintype "passive"))
      (node (ref "C111") (pin "1") (pinfunction "1_1") (pintype "passive"))
      (node (ref "C112") (pin "2") (pinfunction "2_2") (pintype "passive"))
      (node (ref "C113") (pin "2") (pinfunction "2_2") (pintype "passive"))
      (node (ref "C114") (pin "2") (pinfunction "2_2") (pintype "passive"))
      (node (ref "C115") (pin "2") (pinfunction "2_2") (pintype "passive"))
      (node (ref "C116") (pin "1") (pinfunction "1_1") (pintype "passive"))
      (node (ref "C117") (pin "1") (pinfunction "1_1") (pintype "passive"))
      (node (ref "C118") (pin "1") (pinfunction "1_1") (pintype "passive"))
      (node (ref "C120") (pin "2") (pinfunction "2_2") (pintype "passive"))
      (node (ref "C122") (pin "2") (pinfunction "2_2") (pintype "passive"))
      (node (ref "C123") (pin "2") (pinfunction "2_2") (pintype "passive"))
      (node (ref "C124") (pin "2") (pinfunction "2_2") (pintype "passive"))
      (node (ref "C126") (pin "2") (pinfunction "2_2") (pintype "passive"))
      (node (ref "C127") (pin "2") (pinfunction "2_2") (pintype "passive"))
      (node (ref "DS1") (pin "1") (pinfunction "VSS_1") (pintype "bidirectional"))
      (node (ref "DS1") (pin "16") (pinfunction "K_16") (pintype "bidirectional"))
      (node (ref "DS1") (pin "5") (pinfunction "R/W_5") (pintype "bidirectional"))
      (node (ref "IC100") (pin "1") (pinfunction "GND_1") (pintype "power_in"))
      (node (ref "IC101") (pin "1") (pinfunction "C_1") (pintype "passive"))
      (node (ref "IC102") (pin "5") (pinfunction "LDAC_5") (pintype "input"))
      (node (ref "IC102") (pin "7") (pinfunction "AVSS_7") (pintype "power_in"))
      (node (ref "IC103") (pin "1") (pinfunction "C_1") (pintype "passive"))
      (node (ref "IC104") (pin "10") (pinfunction "SER_10") (pintype "input"))
      (node (ref "IC104") (pin "15") (pinfunction "INH_15") (pintype "input"))
      (node (ref "IC104") (pin "5") (pinfunction "G_5") (pintype "input"))
      (node (ref "IC104") (pin "6") (pinfunction "H_6") (pintype "input"))
      (node (ref "IC104") (pin "8") (pinfunction "GND_8") (pintype "power_in"))
      (node (ref "IC105") (pin "18") (pinfunction "GND_18") (pintype "power_in"))
      (node (ref "IC105") (pin "28") (pinfunction "GND_28") (pintype "power_in"))
      (node (ref "IC105") (pin "39") (pinfunction "GND_39") (pintype "power_in"))
      (node (ref "IC105") (pin "6") (pinfunction "GND_6") (pintype "power_in"))
      (node (ref "IC106") (pin "10") (pinfunction "+IN_10") (pintype "input"))
      (node (ref "IC106") (pin "12") (pinfunction "+IN_12") (pintype "input"))
      (node (ref "IC106") (pin "3") (pinfunction "+IN_3") (pintype "input"))
      (node (ref "IC106") (pin "5") (pinfunction "+IN_5") (pintype "input"))
      (node (ref "IC107") (pin "10") (pinfunction "+IN_10") (pintype "input"))
      (node (ref "IC107") (pin "12") (pinfunction "+IN_12") (pintype "input"))
      (node (ref "IC107") (pin "3") (pinfunction "+IN_3") (pintype "input"))
      (node (ref "IC107") (pin "5") (pinfunction "+IN_5") (pintype "input"))
      (node (ref "IC108") (pin "3") (pinfunction "+IN_3") (pintype "input"))
      (node (ref "IC108") (pin "4") (pinfunction "V-_4") (pintype "power_in"))
      (node (ref "IC109") (pin "13") (pinfunction "G_13") (pintype "input"))
      (node (ref "IC109") (pin "8") (pinfunction "GND_8") (pintype "power_in"))
      (node (ref "J1") (pin "P1") (pinfunction "1_P1") (pintype "passive"))
      (node (ref "J10") (pin "P1") (pinfunction "1_P1") (pintype "passive"))
      (node (ref "J10") (pin "P2") (pinfunction "2_P2") (pintype "passive"))
      (node (ref "J100") (pin "3") (pinfunction "3_3") (pintype "passive"))
      (node (ref "J100") (pin "4") (pinfunction "4_4") (pintype "passive"))
      (node (ref "J100") (pin "5") (pinfunction "5_5") (pintype "passive"))
      (node (ref "J100") (pin "6") (pinfunction "6_6") (pintype "passive"))
      (node (ref "J100") (pin "7") (pinfunction "7_7") (pintype "passive"))
      (node (ref "J100") (pin "8") (pinfunction "8_8") (pintype "passive"))
      (node (ref "J2") (pin "P1") (pinfunction "1_P1") (pintype "passive"))
      (node (ref "J3") (pin "P1") (pinfunction "1_P1") (pintype "passive"))
      (node (ref "J4") (pin "P1") (pinfunction "1_P1") (pintype "passive"))
      (node (ref "J5") (pin "P1") (pinfunction "1_P1") (pintype "passive"))
      (node (ref "J6") (pin "P1") (pinfunction "1_P1") (pintype "passive"))
      (node (ref "J7") (pin "P1") (pinfunction "1_P1") (pintype "passive"))
      (node (ref "J8") (pin "P1") (pinfunction "1_P1") (pintype "passive"))
      (node (ref "J9") (pin "P1") (pinfunction "1_P1") (pintype "passive"))
      (node (ref "LED1") (pin "K") (pinfunction "C_K") (pintype "passive"))
      (node (ref "LED2") (pin "K") (pinfunction "C_K") (pintype "passive"))
      (node (ref "LED3") (pin "K") (pinfunction "C_K") (pintype "passive"))
      (node (ref "LED4") (pin "K") (pinfunction "C_K") (pintype "passive"))
      (node (ref "LED5") (pin "K") (pinfunction "C_K") (pintype "passive"))
      (node (ref "LED6") (pin "K") (pinfunction "C_K") (pintype "passive"))
      (node (ref "OK100") (pin "5") (pinfunction "GND_5") (pintype "passive"))
      (node (ref "Q101") (pin "E") (pinfunction "E_E") (pintype "passive"))
      (node (ref "R101") (pin "2") (pinfunction "2_2") (pintype "passive"))
      (node (ref "R103") (pin "3") (pinfunction "A_3") (pintype "passive"))
      (node (ref "R132") (pin "1") (pinfunction "1_1") (pintype "passive"))
      (node (ref "S1") (pin "1") (pinfunction "1_1") (pintype "passive"))
      (node (ref "S1") (pin "2") (pinfunction "2_2") (pintype "passive"))
      (node (ref "S2") (pin "1") (pinfunction "1_1") (pintype "passive"))
      (node (ref "S2") (pin "2") (pinfunction "2_2") (pintype "passive"))
      (node (ref "S3") (pin "1") (pinfunction "1_1") (pintype "passive"))
      (node (ref "S3") (pin "2") (pinfunction "2_2") (pintype "passive"))
      (node (ref "S4") (pin "1") (pinfunction "1_1") (pintype "passive"))
      (node (ref "S4") (pin "2") (pinfunction "2_2") (pintype "passive"))
      (node (ref "S5") (pin "1") (pinfunction "1_1") (pintype "passive"))
      (node (ref "S5") (pin "2") (pinfunction "2_2") (pintype "passive"))
      (node (ref "S6") (pin "1") (pinfunction "1_1") (pintype "passive"))
      (node (ref "S6") (pin "2") (pinfunction "2_2") (pintype "passive"))
      (node (ref "SW1") (pin "C") (pinfunction "C_C") (pintype "passive"))
      (node (ref "SW1") (pin "D") (pinfunction "1_D") (pintype "passive"))
      (node (ref "U100") (pin "6") (pinfunction "6_6") (pintype "passive"))
    )
    (net (code "16") (name "IO_ENABLE") (class "Default")
      (node (ref "IC104") (pin "1") (pinfunction "SH/~{LD}_1") (pintype "input"))
      (node (ref "IC105") (pin "23") (pinfunction "(PCINT20/TDO)PC4_23") (pintype "output"))
      (node (ref "IC109") (pin "12") (pinfunction "RCK_12") (pintype "input"))
    )
    (net (code "17") (name "IO_INPUT") (class "Default")
      (node (ref "IC104") (pin "9") (pinfunction "QH_9") (pintype "output"))
      (node (ref "IC105") (pin "25") (pinfunction "(PCINT22/TOSC1)PC6_25") (pintype "output"))
    )
    (net (code "18") (name "IO_OUTPUT") (class "Default")
      (node (ref "IC105") (pin "24") (pinfunction "(PCINT21/TDI)PC5_24") (pintype "output"))
      (node (ref "IC109") (pin "14") (pinfunction "SER_14") (pintype "input"))
    )
    (net (code "19") (name "IO_SCK") (class "Default")
      (node (ref "IC104") (pin "2") (pinfunction "CLK_2") (pintype "input"))
      (node (ref "IC105") (pin "26") (pinfunction "(PCINT23/TOSC2)PC7_26") (pintype "output"))
      (node (ref "IC109") (pin "11") (pinfunction "SCK_11") (pintype "input"))
    )
    (net (code "20") (name "LCD_DATA4") (class "Default")
      (node (ref "DS1") (pin "11") (pinfunction "D4_11") (pintype "bidirectional"))
      (node (ref "IC105") (pin "33") (pinfunction "(PCINT4/ADC4)PA4_33") (pintype "bidirectional"))
    )
    (net (code "21") (name "LCD_DATA5") (class "Default")
      (node (ref "DS1") (pin "12") (pinfunction "D5_12") (pintype "bidirectional"))
      (node (ref "IC105") (pin "32") (pinfunction "(PCINT5/ADC5)PA5_32") (pintype "bidirectional"))
    )
    (net (code "22") (name "LCD_DATA6") (class "Default")
      (node (ref "DS1") (pin "13") (pinfunction "D6_13") (pintype "bidirectional"))
      (node (ref "IC105") (pin "31") (pinfunction "(PCINT6/ADC6)PA6_31") (pintype "bidirectional"))
    )
    (net (code "23") (name "LCD_DATA7") (class "Default")
      (node (ref "DS1") (pin "14") (pinfunction "D7_14") (pintype "bidirectional"))
      (node (ref "IC105") (pin "30") (pinfunction "(PCINT7/ADC7)PA7_30") (pintype "bidirectional"))
    )
    (net (code "24") (name "LCD_ENABLE") (class "Default")
      (node (ref "DS1") (pin "6") (pinfunction "E_6") (pintype "bidirectional"))
      (node (ref "IC105") (pin "35") (pinfunction "(PCINT2/ADC2)PA2_35") (pintype "bidirectional"))
    )
    (net (code "25") (name "LCD_RS") (class "Default")
      (node (ref "DS1") (pin "4") (pinfunction "RS_4") (pintype "bidirectional"))
      (node (ref "IC105") (pin "34") (pinfunction "(PCINT3/ADC3)PA3_34") (pintype "bidirectional"))
    )
    (net (code "26") (name "MIDI_IN") (class "Default")
      (node (ref "IC105") (pin "9") (pinfunction "(PCINT24/RXD0)PD0_9") (pintype "bidirectional"))
      (node (ref "OK100") (pin "6") (pinfunction "VO_6") (pintype "passive"))
      (node (ref "R117") (pin "1") (pinfunction "1_1") (pintype "passive"))
    )
    (net (code "27") (name "MISO") (class "Default")
      (node (ref "IC105") (pin "2") (pinfunction "(PCINT14/MISO)PB6_2") (pintype "bidirectional"))
      (node (ref "U100") (pin "1") (pinfunction "1_1") (pintype "passive"))
    )
    (net (code "28") (name "MOSI") (class "Default")
      (node (ref "IC102") (pin "4") (pinfunction "SDI_4") (pintype "input"))
      (node (ref "IC105") (pin "1") (pinfunction "(PCINT13/MOSI)PB5_1") (pintype "bidirectional"))
      (node (ref "U100") (pin "4") (pinfunction "4_4") (pintype "passive"))
    )
    (net (code "29") (name "Net-(C107-Pad-)") (class "Default")
      (node (ref "C107") (pin "-") (pinfunction "-_-") (pintype "passive"))
      (node (ref "R129") (pin "1") (pinfunction "1_1") (pintype "passive"))
    )
    (net (code "30") (name "Net-(C128-Pad-)") (class "Default")
      (node (ref "C128") (pin "-") (pinfunction "-_-") (pintype "passive"))
      (node (ref "R152") (pin "1") (pinfunction "1_1") (pintype "passive"))
    )
    (net (code "31") (name "Net-(D100-PadA)") (class "Default")
      (node (ref "D100") (pin "A") (pinfunction "A_A") (pintype "passive"))
      (node (ref "J100") (pin "1") (pinfunction "1_1") (pintype "passive"))
      (node (ref "J100") (pin "2") (pinfunction "2_2") (pintype "passive"))
    )
    (net (code "32") (name "Net-(D101-PadC)") (class "Default")
      (node (ref "D101") (pin "C") (pinfunction "C_C") (pintype "passive"))
      (node (ref "J100") (pin "10") (pinfunction "10_10") (pintype "passive"))
      (node (ref "J100") (pin "9") (pinfunction "9_9") (pintype "passive"))
    )
    (net (code "33") (name "Net-(DS1-A)") (class "Default")
      (node (ref "DS1") (pin "15") (pinfunction "A_15") (pintype "bidirectional"))
      (node (ref "R102") (pin "2") (pinfunction "2_2") (pintype "passive"))
    )
    (net (code "34") (name "Net-(DS1-VO)") (class "Default")
      (node (ref "DS1") (pin "2") (pinfunction "VO_2") (pintype "bidirectional"))
      (node (ref "R103") (pin "2") (pinfunction "S_2") (pintype "passive"))
    )
    (net (code "35") (name "Net-(IC104A-A)") (class "Default")
      (node (ref "IC104") (pin "11") (pinfunction "A_11") (pintype "input"))
      (node (ref "R164") (pin "1") (pinfunction "1_1") (pintype "passive"))
      (node (ref "S1") (pin "3") (pinfunction "3_3") (pintype "passive"))
      (node (ref "S1") (pin "4") (pinfunction "4_4") (pintype "passive"))
    )
    (net (code "36") (name "Net-(IC104A-B)") (class "Default")
      (node (ref "IC104") (pin "12") (pinfunction "B_12") (pintype "input"))
      (node (ref "R167") (pin "1") (pinfunction "1_1") (pintype "passive"))
      (node (ref "S2") (pin "3") (pinfunction "3_3") (pintype "passive"))
      (node (ref "S2") (pin "4") (pinfunction "4_4") (pintype "passive"))
    )
    (net (code "37") (name "Net-(IC104A-C)") (class "Default")
      (node (ref "IC104") (pin "13") (pinfunction "C_13") (pintype "input"))
      (node (ref "R166") (pin "1") (pinfunction "1_1") (pintype "passive"))
      (node (ref "S3") (pin "3") (pinfunction "3_3") (pintype "passive"))
      (node (ref "S3") (pin "4") (pinfunction "4_4") (pintype "passive"))
    )
    (net (code "38") (name "Net-(IC104A-D)") (class "Default")
      (node (ref "IC104") (pin "14") (pinfunction "D_14") (pintype "input"))
      (node (ref "R165") (pin "1") (pinfunction "1_1") (pintype "passive"))
      (node (ref "S4") (pin "3") (pinfunction "3_3") (pintype "passive"))
      (node (ref "S4") (pin "4") (pinfunction "4_4") (pintype "passive"))
    )
    (net (code "39") (name "Net-(IC104A-E)") (class "Default")
      (node (ref "IC104") (pin "3") (pinfunction "E_3") (pintype "input"))
      (node (ref "R168") (pin "1") (pinfunction "1_1") (pintype "passive"))
      (node (ref "S5") (pin "3") (pinfunction "3_3") (pintype "passive"))
      (node (ref "S5") (pin "4") (pinfunction "4_4") (pintype "passive"))
    )
    (net (code "40") (name "Net-(IC104A-F)") (class "Default")
      (node (ref "IC104") (pin "4") (pinfunction "F_4") (pintype "input"))
      (node (ref "R163") (pin "1") (pinfunction "1_1") (pintype "passive"))
      (node (ref "S6") (pin "3") (pinfunction "3_3") (pintype "passive"))
      (node (ref "S6") (pin "4") (pinfunction "4_4") (pintype "passive"))
    )
    (net (code "41") (name "Net-(IC105-AREF)") (class "Default")
      (node (ref "C114") (pin "1") (pinfunction "1_1") (pintype "passive"))
      (node (ref "IC105") (pin "29") (pinfunction "AREF_29") (pintype "passive"))
    )
    (net (code "42") (name "Net-(IC105-XTAL1)") (class "Default")
      (node (ref "C116") (pin "2") (pinfunction "2_2") (pintype "passive"))
      (node (ref "IC105") (pin "8") (pinfunction "XTAL1_8") (pintype "bidirectional"))
      (node (ref "Q100") (pin "1") (pinfunction "1_1") (pintype "passive"))
    )
    (net (code "43") (name "Net-(IC105-XTAL2)") (class "Default")
      (node (ref "C111") (pin "2") (pinfunction "2_2") (pintype "passive"))
      (node (ref "IC105") (pin "7") (pinfunction "XTAL2_7") (pintype "bidirectional"))
      (node (ref "Q100") (pin "2") (pinfunction "2_2") (pintype "passive"))
    )
    (net (code "44") (name "Net-(IC106A--IN)") (class "Default")
      (node (ref "IC106") (pin "2") (pinfunction "-IN_2") (pintype "input"))
      (node (ref "R123") (pin "1") (pinfunction "1_1") (pintype "passive"))
      (node (ref "R130") (pin "2") (pinfunction "2_2") (pintype "passive"))
    )
    (net (code "45") (name "Net-(IC106B--IN)") (class "Default")
      (node (ref "IC106") (pin "6") (pinfunction "-IN_6") (pintype "input"))
      (node (ref "R124") (pin "1") (pinfunction "1_1") (pintype "passive"))
      (node (ref "R128") (pin "2") (pinfunction "2_2") (pintype "passive"))
    )
    (net (code "46") (name "Net-(IC106C--IN)") (class "Default")
      (node (ref "IC106") (pin "9") (pinfunction "-IN_9") (pintype "input"))
      (node (ref "R109") (pin "2") (pinfunction "2_2") (pintype "passive"))
      (node (ref "R114") (pin "1") (pinfunction "1_1") (pintype "passive"))
    )
    (net (code "47") (name "Net-(IC106C-OUT)") (class "Default")
      (node (ref "IC106") (pin "8") (pinfunction "OUT_8") (pintype "output"))
      (node (ref "R114") (pin "2") (pinfunction "2_2") (pintype "passive"))
      (node (ref "R148") (pin "1") (pinfunction "1_1") (pintype "passive"))
    )
    (net (code "48") (name "Net-(IC106D--IN)") (class "Default")
      (node (ref "IC106") (pin "13") (pinfunction "-IN_13") (pintype "input"))
      (node (ref "R147") (pin "1") (pinfunction "1_1") (pintype "passive"))
      (node (ref "R150") (pin "2") (pinfunction "2_2") (pintype "passive"))
    )
    (net (code "49") (name "Net-(IC106D-OUT)") (class "Default")
      (node (ref "IC106") (pin "14") (pinfunction "OUT_14") (pintype "output"))
      (node (ref "R147") (pin "2") (pinfunction "2_2") (pintype "passive"))
      (node (ref "R151") (pin "1") (pinfunction "1_1") (pintype "passive"))
    )
    (net (code "50") (name "Net-(IC107A--IN)") (class "Default")
      (node (ref "IC107") (pin "2") (pinfunction "-IN_2") (pintype "input"))
      (node (ref "R121") (pin "1") (pinfunction "1_1") (pintype "passive"))
      (node (ref "R125") (pin "2") (pinfunction "2_2") (pintype "passive"))
    )
    (net (code "51") (name "Net-(IC107A-OUT)") (class "Default")
      (node (ref "IC107") (pin "1") (pinfunction "OUT_1") (pintype "output"))
      (node (ref "R121") (pin "2") (pinfunction "2_2") (pintype "passive"))
      (node (ref "R146") (pin "1") (pinfunction "1_1") (pintype "passive"))
    )
    (net (code "52") (name "Net-(IC107B--IN)") (class "Default")
      (node (ref "C125") (pin "1") (pinfunction "1_1") (pintype "passive"))
      (node (ref "IC107") (pin "6") (pinfunction "-IN_6") (pintype "input"))
      (node (ref "R126") (pin "1") (pinfunction "1_1") (pintype "passive"))
      (node (ref "R129") (pin "2") (pinfunction "2_2") (pintype "passive"))
    )
    (net (code "53") (name "Net-(IC107B-OUT)") (class "Default")
      (node (ref "IC107") (pin "7") (pinfunction "OUT_7") (pintype "output"))
      (node (ref "R127") (pin "1") (pinfunction "1_1") (pintype "passive"))
    )
    (net (code "54") (name "Net-(IC107C--IN)") (class "Default")
      (node (ref "C119") (pin "1") (pinfunction "1_1") (pintype "passive"))
      (node (ref "IC107") (pin "9") (pinfunction "-IN_9") (pintype "input"))
      (node (ref "R111") (pin "2") (pinfunction "2_2") (pintype "passive"))
      (node (ref "R112") (pin "1") (pinfunction "1_1") (pintype "passive"))
      (node (ref "R113") (pin "2") (pinfunction "2_2") (pintype "passive"))
    )
    (net (code "55") (name "Net-(IC107C-OUT)") (class "Default")
      (node (ref "IC107") (pin "8") (pinfunction "OUT_8") (pintype "output"))
      (node (ref "R115") (pin "1") (pinfunction "1_1") (pintype "passive"))
    )
    (net (code "56") (name "Net-(IC107D--IN)") (class "Default")
      (node (ref "IC107") (pin "13") (pinfunction "-IN_13") (pintype "input"))
      (node (ref "R116") (pin "1") (pinfunction "1_1") (pintype "passive"))
      (node (ref "R118") (pin "2") (pinfunction "2_2") (pintype "passive"))
    )
    (net (code "57") (name "Net-(IC107D-OUT)") (class "Default")
      (node (ref "IC107") (pin "14") (pinfunction "OUT_14") (pintype "output"))
      (node (ref "R116") (pin "2") (pinfunction "2_2") (pintype "passive"))
      (node (ref "R149") (pin "1") (pinfunction "1_1") (pintype "passive"))
    )
    (net (code "58") (name "Net-(IC108A--IN)") (class "Default")
      (node (ref "IC108") (pin "2") (pinfunction "-IN_2") (pintype "input"))
      (node (ref "R120") (pin "1") (pinfunction "1_1") (pintype "passive"))
      (node (ref "R122") (pin "2") (pinfunction "2_2") (pintype "passive"))
    )
    (net (code "59") (name "Net-(IC108B-+IN)") (class "Default")
      (node (ref "C124") (pin "1") (pinfunction "1_1") (pintype "passive"))
      (node (ref "IC108") (pin "5") (pinfunction "+IN_5") (pintype "input"))
      (node (ref "R131") (pin "1") (pinfunction "1_1") (pintype "passive"))
      (node (ref "R132") (pin "2") (pinfunction "2_2") (pintype "passive"))
    )
    (net (code "60") (name "Net-(IC108B--IN)") (class "Default")
      (node (ref "C121") (pin "1") (pinfunction "1_1") (pintype "passive"))
      (node (ref "IC108") (pin "6") (pinfunction "-IN_6") (pintype "input"))
      (node (ref "R119") (pin "1") (pinfunction "1_1") (pintype "passive"))
      (node (ref "R152") (pin "2") (pinfunction "2_2") (pintype "passive"))
    )
    (net (code "61") (name "Net-(IC109A-QA)") (class "Default")
      (node (ref "IC109") (pin "15") (pinfunction "QA_15") (pintype "tri_state"))
      (node (ref "R158") (pin "1") (pinfunction "1_1") (pintype "passive"))
    )
    (net (code "62") (name "Net-(IC109A-QB)") (class "Default")
      (node (ref "IC109") (pin "1") (pinfunction "QB_1") (pintype "tri_state"))
      (node (ref "R161") (pin "1") (pinfunction "1_1") (pintype "passive"))
    )
    (net (code "63") (name "Net-(IC109A-QC)") (class "Default")
      (node (ref "IC109") (pin "2") (pinfunction "QC_2") (pintype "tri_state"))
      (node (ref "R160") (pin "1") (pinfunction "1_1") (pintype "passive"))
    )
    (net (code "64") (name "Net-(IC109A-QD)") (class "Default")
      (node (ref "IC109") (pin "3") (pinfunction "QD_3") (pintype "tri_state"))
      (node (ref "R162") (pin "1") (pinfunction "1_1") (pintype "passive"))
    )
    (net (code "65") (name "Net-(IC109A-QE)") (class "Default")
      (node (ref "IC109") (pin "4") (pinfunction "QE_4") (pintype "tri_state"))
      (node (ref "R159") (pin "1") (pinfunction "1_1") (pintype "passive"))
    )
    (net (code "66") (name "Net-(IC109A-QF)") (class "Default")
      (node (ref "IC109") (pin "5") (pinfunction "QF_5") (pintype "tri_state"))
      (node (ref "R157") (pin "1") (pinfunction "1_1") (pintype "passive"))
    )
    (net (code "67") (name "Net-(J1-3)") (class "Default")
      (node (ref "J1") (pin "P3") (pinfunction "3_P3") (pintype "passive"))
      (node (ref "R148") (pin "2") (pinfunction "2_2") (pintype "passive"))
    )
    (net (code "68") (name "Net-(J2-3)") (class "Default")
      (node (ref "J2") (pin "P3") (pinfunction "3_P3") (pintype "passive"))
      (node (ref "R151") (pin "2") (pinfunction "2_2") (pintype "passive"))
    )
    (net (code "69") (name "Net-(J3-3)") (class "Default")
      (node (ref "J3") (pin "P3") (pinfunction "3_P3") (pintype "passive"))
      (node (ref "R149") (pin "2") (pinfunction "2_2") (pintype "passive"))
    )
    (net (code "70") (name "Net-(J4-3)") (class "Default")
      (node (ref "J4") (pin "P3") (pinfunction "3_P3") (pintype "passive"))
      (node (ref "R146") (pin "2") (pinfunction "2_2") (pintype "passive"))
    )
    (net (code "71") (name "Net-(J5-3)") (class "Default")
      (node (ref "J5") (pin "P3") (pinfunction "3_P3") (pintype "passive"))
      (node (ref "R153") (pin "2") (pinfunction "2_2") (pintype "passive"))
    )
    (net (code "72") (name "Net-(J6-3)") (class "Default")
      (node (ref "J6") (pin "P3") (pinfunction "3_P3") (pintype "passive"))
      (node (ref "R154") (pin "2") (pinfunction "2_2") (pintype "passive"))
    )
    (net (code "73") (name "Net-(J7-3)") (class "Default")
      (node (ref "C119") (pin "2") (pinfunction "2_2") (pintype "passive"))
      (node (ref "J7") (pin "P3") (pinfunction "3_P3") (pintype "passive"))
      (node (ref "R112") (pin "2") (pinfunction "2_2") (pintype "passive"))
      (node (ref "R115") (pin "2") (pinfunction "2_2") (pintype "passive"))
    )
    (net (code "74") (name "Net-(J8-3)") (class "Default")
      (node (ref "C125") (pin "2") (pinfunction "2_2") (pintype "passive"))
      (node (ref "J8") (pin "P3") (pinfunction "3_P3") (pintype "passive"))
      (node (ref "R126") (pin "2") (pinfunction "2_2") (pintype "passive"))
      (node (ref "R127") (pin "2") (pinfunction "2_2") (pintype "passive"))
    )
    (net (code "75") (name "Net-(J9-3)") (class "Default")
      (node (ref "C128") (pin "+") (pinfunction "+_+") (pintype "passive"))
      (node (ref "J9") (pin "P3") (pinfunction "3_P3") (pintype "passive"))
      (node (ref "R122") (pin "1") (pinfunction "1_1") (pintype "passive"))
    )
    (net (code "76") (name "Net-(J10-3)") (class "Default")
      (node (ref "J10") (pin "P3") (pinfunction "3_P3") (pintype "passive"))
      (node (ref "R155") (pin "1") (pinfunction "1_1") (pintype "passive"))
    )
    (net (code "77") (name "Net-(LED1-PadA)") (class "Default")
      (node (ref "LED1") (pin "A") (pinfunction "A_A") (pintype "passive"))
      (node (ref "R158") (pin "2") (pinfunction "2_2") (pintype "passive"))
    )
    (net (code "78") (name "Net-(LED2-PadA)") (class "Default")
      (node (ref "LED2") (pin "A") (pinfunction "A_A") (pintype "passive"))
      (node (ref "R161") (pin "2") (pinfunction "2_2") (pintype "passive"))
    )
    (net (code "79") (name "Net-(LED3-PadA)") (class "Default")
      (node (ref "LED3") (pin "A") (pinfunction "A_A") (pintype "passive"))
      (node (ref "R160") (pin "2") (pinfunction "2_2") (pintype "passive"))
    )
    (net (code "80") (name "Net-(LED4-PadA)") (class "Default")
      (node (ref "LED4") (pin "A") (pinfunction "A_A") (pintype "passive"))
      (node (ref "R162") (pin "2") (pinfunction "2_2") (pintype "passive"))
    )
    (net (code "81") (name "Net-(LED5-PadA)") (class "Default")
      (node (ref "LED5") (pin "A") (pinfunction "A_A") (pintype "passive"))
      (node (ref "R159") (pin "2") (pinfunction "2_2") (pintype "passive"))
    )
    (net (code "82") (name "Net-(LED6-PadA)") (class "Default")
      (node (ref "LED6") (pin "A") (pinfunction "A_A") (pintype "passive"))
      (node (ref "R157") (pin "2") (pinfunction "2_2") (pintype "passive"))
    )
    (net (code "83") (name "Net-(OK100-A)") (class "Default")
      (node (ref "D102") (pin "C") (pinfunction "C_C") (pintype "passive"))
      (node (ref "OK100") (pin "2") (pinfunction "A_2") (pintype "passive"))
      (node (ref "R137") (pin "2") (pinfunction "2_2") (pintype "passive"))
    )
    (net (code "84") (name "Net-(OK100-C)") (class "Default")
      (node (ref "D102") (pin "A") (pinfunction "A_A") (pintype "passive"))
      (node (ref "OK100") (pin "3") (pinfunction "C_3") (pintype "passive"))
      (node (ref "U$1") (pin "P2") (pinfunction "2_P2") (pintype "passive"))
    )
    (net (code "85") (name "Net-(Q101-PadB)") (class "Default")
      (node (ref "Q101") (pin "B") (pinfunction "B_B") (pintype "passive"))
      (node (ref "R155") (pin "2") (pinfunction "2_2") (pintype "passive"))
    )
    (net (code "86") (name "Net-(R100-Pad2)") (class "Default")
      (node (ref "R100") (pin "2") (pinfunction "2_2") (pintype "passive"))
      (node (ref "R101") (pin "1") (pinfunction "1_1") (pintype "passive"))
      (node (ref "R102") (pin "1") (pinfunction "1_1") (pintype "passive"))
    )
    (net (code "87") (name "Net-(R107-E)") (class "Default")
      (node (ref "R107") (pin "1") (pinfunction "E_1") (pintype "passive"))
      (node (ref "R113") (pin "1") (pinfunction "1_1") (pintype "passive"))
    )
    (net (code "88") (name "Net-(R108-E)") (class "Default")
      (node (ref "R108") (pin "1") (pinfunction "E_1") (pintype "passive"))
      (node (ref "R110") (pin "1") (pinfunction "1_1") (pintype "passive"))
    )
    (net (code "89") (name "Net-(R110-Pad2)") (class "Default")
      (node (ref "R110") (pin "2") (pinfunction "2_2") (pintype "passive"))
      (node (ref "R111") (pin "1") (pinfunction "1_1") (pintype "passive"))
    )
    (net (code "90") (name "Net-(R133-A)") (class "Default")
      (node (ref "R133") (pin "3") (pinfunction "A_3") (pintype "passive"))
      (node (ref "R144") (pin "2") (pinfunction "2_2") (pintype "passive"))
    )
    (net (code "91") (name "Net-(R133-E)") (class "Default")
      (node (ref "R133") (pin "1") (pinfunction "E_1") (pintype "passive"))
      (node (ref "R145") (pin "2") (pinfunction "2_2") (pintype "passive"))
    )
    (net (code "92") (name "Net-(R133-S)") (class "Default")
      (node (ref "R125") (pin "1") (pinfunction "1_1") (pintype "passive"))
      (node (ref "R133") (pin "2") (pinfunction "S_2") (pintype "passive"))
    )
    (net (code "93") (name "Net-(R134-A)") (class "Default")
      (node (ref "R134") (pin "3") (pinfunction "A_3") (pintype "passive"))
      (node (ref "R139") (pin "2") (pinfunction "2_2") (pintype "passive"))
    )
    (net (code "94") (name "Net-(R134-E)") (class "Default")
      (node (ref "R134") (pin "1") (pinfunction "E_1") (pintype "passive"))
      (node (ref "R138") (pin "2") (pinfunction "2_2") (pintype "passive"))
    )
    (net (code "95") (name "Net-(R134-S)") (class "Default")
      (node (ref "R118") (pin "1") (pinfunction "1_1") (pintype "passive"))
      (node (ref "R134") (pin "2") (pinfunction "S_2") (pintype "passive"))
    )
    (net (code "96") (name "Net-(R135-A)") (class "Default")
      (node (ref "R135") (pin "3") (pinfunction "A_3") (pintype "passive"))
      (node (ref "R140") (pin "2") (pinfunction "2_2") (pintype "passive"))
    )
    (net (code "97") (name "Net-(R135-E)") (class "Default")
      (node (ref "R135") (pin "1") (pinfunction "E_1") (pintype "passive"))
      (node (ref "R141") (pin "2") (pinfunction "2_2") (pintype "passive"))
    )
    (net (code "98") (name "Net-(R135-S)") (class "Default")
      (node (ref "R135") (pin "2") (pinfunction "S_2") (pintype "passive"))
      (node (ref "R150") (pin "1") (pinfunction "1_1") (pintype "passive"))
    )
    (net (code "99") (name "Net-(R136-A)") (class "Default")
      (node (ref "R136") (pin "3") (pinfunction "A_3") (pintype "passive"))
      (node (ref "R142") (pin "2") (pinfunction "2_2") (pintype "passive"))
    )
    (net (code "100") (name "Net-(R136-E)") (class "Default")
      (node (ref "R136") (pin "1") (pinfunction "E_1") (pintype "passive"))
      (node (ref "R143") (pin "2") (pinfunction "2_2") (pintype "passive"))
    )
    (net (code "101") (name "Net-(R136-S)") (class "Default")
      (node (ref "R109") (pin "1") (pinfunction "1_1") (pintype "passive"))
      (node (ref "R136") (pin "2") (pinfunction "S_2") (pintype "passive"))
    )
    (net (code "102") (name "Net-(U$1-3)") (class "Default")
      (node (ref "R137") (pin "1") (pinfunction "1_1") (pintype "passive"))
      (node (ref "U$1") (pin "P3") (pinfunction "3_P3") (pintype "passive"))
    )
    (net (code "103") (name "PITCH_DETECTOR") (class "Default")
      (node (ref "IC105") (pin "15") (pinfunction "(PCINT30/OC2B/ICP)PD6_15") (pintype "bidirectional"))
      (node (ref "IC108") (pin "1") (pinfunction "OUT_1") (pintype "output"))
      (node (ref "R120") (pin "2") (pinfunction "2_2") (pintype "passive"))
    )
    (net (code "104") (name "REF_-4.096") (class "Default")
      (node (ref "C108") (pin "1") (pinfunction "1_1") (pintype "passive"))
      (node (ref "IC103") (pin "2") (pinfunction "A_2") (pintype "passive"))
      (node (ref "R106") (pin "2") (pinfunction "2_2") (pintype "passive"))
      (node (ref "R108") (pin "2") (pinfunction "S_2") (pintype "passive"))
      (node (ref "R108") (pin "3") (pinfunction "A_3") (pintype "passive"))
    )
    (net (code "105") (name "REF_-5V") (class "Default")
      (node (ref "C105") (pin "1") (pinfunction "1_1") (pintype "passive"))
      (node (ref "IC101") (pin "2") (pinfunction "A_2") (pintype "passive"))
      (node (ref "R104") (pin "2") (pinfunction "2_2") (pintype "passive"))
      (node (ref "R130") (pin "1") (pinfunction "1_1") (pintype "passive"))
    )
    (net (code "106") (name "RESET") (class "Default")
      (node (ref "C112") (pin "1") (pinfunction "1_1") (pintype "passive"))
      (node (ref "IC105") (pin "4") (pinfunction "RESET_4") (pintype "input"))
      (node (ref "R105") (pin "1") (pinfunction "1_1") (pintype "passive"))
      (node (ref "U100") (pin "5") (pinfunction "5_5") (pintype "passive"))
    )
    (net (code "107") (name "SCK") (class "Default")
      (node (ref "IC102") (pin "3") (pinfunction "SCK_3") (pintype "input"))
      (node (ref "IC105") (pin "3") (pinfunction "(PCINT15/SCK)PB7_3") (pintype "bidirectional"))
      (node (ref "U100") (pin "3") (pinfunction "3_3") (pintype "passive"))
    )
    (net (code "108") (name "SS") (class "Default")
      (node (ref "IC102") (pin "2") (pinfunction "#CS_2") (pintype "input"))
      (node (ref "IC105") (pin "44") (pinfunction "(PCINT12/OC0B/~{SS})PB4_44") (pintype "bidirectional"))
    )
    (net (code "109") (name "VCC") (class "Default")
      (node (ref "C100") (pin "+") (pinfunction "+_+") (pintype "passive"))
      (node (ref "C102") (pin "+") (pinfunction "+_+") (pintype "passive"))
      (node (ref "C122") (pin "1") (pinfunction "1_1") (pintype "passive"))
      (node (ref "C123") (pin "1") (pinfunction "1_1") (pintype "passive"))
      (node (ref "D100") (pin "C") (pinfunction "C_C") (pintype "passive"))
      (node (ref "IC100") (pin "3") (pinfunction "VIN_3") (pintype "input"))
      (node (ref "IC106") (pin "4") (pinfunction "V+_4") (pintype "power_in"))
      (node (ref "IC107") (pin "4") (pinfunction "V+_4") (pintype "power_in"))
    )
    (net (code "110") (name "VEE") (class "Default")
      (node (ref "C109") (pin "-") (pinfunction "-_-") (pintype "passive"))
      (node (ref "C117") (pin "2") (pinfunction "2_2") (pintype "passive"))
      (node (ref "C118") (pin "2") (pinfunction "2_2") (pintype "passive"))
      (node (ref "D101") (pin "A") (pinfunction "A_A") (pintype "passive"))
      (node (ref "IC106") (pin "11") (pinfunction "V-_11") (pintype "power_in"))
      (node (ref "IC107") (pin "11") (pinfunction "V-_11") (pintype "power_in"))
      (node (ref "R104") (pin "1") (pinfunction "1_1") (pintype "passive"))
      (node (ref "R106") (pin "1") (pinfunction "1_1") (pintype "passive"))
    )
    (net (code "111") (name "unconnected-(DS1-D0-Pad7)") (class "Default")
      (node (ref "DS1") (pin "7") (pinfunction "D0_7") (pintype "bidirectional"))
    )
    (net (code "112") (name "unconnected-(DS1-D1-Pad8)") (class "Default")
      (node (ref "DS1") (pin "8") (pinfunction "D1_8") (pintype "bidirectional"))
    )
    (net (code "113") (name "unconnected-(DS1-D2-Pad9)") (class "Default")
      (node (ref "DS1") (pin "9") (pinfunction "D2_9") (pintype "bidirectional"))
    )
    (net (code "114") (name "unconnected-(DS1-D3-Pad10)") (class "Default")
      (node (ref "DS1") (pin "10") (pinfunction "D3_10") (pintype "bidirectional"))
    )
    (net (code "115") (name "unconnected-(IC104A-~{QH}-Pad7)") (class "Default")
      (node (ref "IC104") (pin "7") (pinfunction "~{QH}_7") (pintype "output"))
    )
    (net (code "116") (name "unconnected-(IC105-(PCINT1{slash}ADC1)PA1-Pad36)") (class "Default")
      (node (ref "IC105") (pin "36") (pinfunction "(PCINT1/ADC1)PA1_36") (pintype "bidirectional"))
    )
    (net (code "117") (name "unconnected-(IC105-(PCINT8{slash}XCK0{slash}T0)PB0-Pad40)") (class "Default")
      (node (ref "IC105") (pin "40") (pinfunction "(PCINT8/XCK0/T0)PB0_40") (pintype "bidirectional"))
    )
    (net (code "118") (name "unconnected-(IC105-(PCINT9{slash}CLKO{slash}T1)PB1-Pad41)") (class "Default")
      (node (ref "IC105") (pin "41") (pinfunction "(PCINT9/CLKO/T1)PB1_41") (pintype "bidirectional"))
    )
    (net (code "119") (name "unconnected-(IC105-(PCINT10{slash}INT2{slash}AIN0)PB2-Pad42)") (class "Default")
      (node (ref "IC105") (pin "42") (pinfunction "(PCINT10/INT2/AIN0)PB2_42") (pintype "bidirectional"))
    )
    (net (code "120") (name "unconnected-(IC105-(PCINT11{slash}OC0A{slash}AIN1)PB3-Pad43)") (class "Default")
      (node (ref "IC105") (pin "43") (pinfunction "(PCINT11/OC0A/AIN1)PB3_43") (pintype "bidirectional"))
    )
    (net (code "121") (name "unconnected-(IC105-(PCINT19{slash}TMS)PC3-Pad22)") (class "Default")
      (node (ref "IC105") (pin "22") (pinfunction "(PCINT19/TMS)PC3_22") (pintype "output"))
    )
    (net (code "122") (name "unconnected-(IC105-(PCINT25{slash}TXD0)PD1-Pad10)") (class "Default")
      (node (ref "IC105") (pin "10") (pinfunction "(PCINT25/TXD0)PD1_10") (pintype "bidirectional"))
    )
    (net (code "123") (name "unconnected-(IC105-(PCINT29{slash}OC1A)PD5-Pad14)") (class "Default")
      (node (ref "IC105") (pin "14") (pinfunction "(PCINT29/OC1A)PD5_14") (pintype "bidirectional"))
    )
    (net (code "124") (name "unconnected-(IC105-(PCINT31{slash}OC2A)PD7-Pad16)") (class "Default")
      (node (ref "IC105") (pin "16") (pinfunction "(PCINT31/OC2A)PD7_16") (pintype "bidirectional"))
    )
    (net (code "125") (name "unconnected-(IC109A-QG-Pad6)") (class "Default")
      (node (ref "IC109") (pin "6") (pinfunction "QG_6") (pintype "tri_state"))
    )
    (net (code "126") (name "unconnected-(IC109A-QH*-Pad9)") (class "Default")
      (node (ref "IC109") (pin "9") (pinfunction "QH*_9") (pintype "tri_state"))
    )
    (net (code "127") (name "unconnected-(IC109A-QH-Pad7)") (class "Default")
      (node (ref "IC109") (pin "7") (pinfunction "QH_7") (pintype "tri_state"))
    )
    (net (code "128") (name "unconnected-(J1-2-PadP2)") (class "Default")
      (node (ref "J1") (pin "P2") (pinfunction "2_P2") (pintype "passive"))
    )
    (net (code "129") (name "unconnected-(J2-2-PadP2)") (class "Default")
      (node (ref "J2") (pin "P2") (pinfunction "2_P2") (pintype "passive"))
    )
    (net (code "130") (name "unconnected-(J3-2-PadP2)") (class "Default")
      (node (ref "J3") (pin "P2") (pinfunction "2_P2") (pintype "passive"))
    )
    (net (code "131") (name "unconnected-(J4-2-PadP2)") (class "Default")
      (node (ref "J4") (pin "P2") (pinfunction "2_P2") (pintype "passive"))
    )
    (net (code "132") (name "unconnected-(J5-2-PadP2)") (class "Default")
      (node (ref "J5") (pin "P2") (pinfunction "2_P2") (pintype "passive"))
    )
    (net (code "133") (name "unconnected-(J6-2-PadP2)") (class "Default")
      (node (ref "J6") (pin "P2") (pinfunction "2_P2") (pintype "passive"))
    )
    (net (code "134") (name "unconnected-(J7-2-PadP2)") (class "Default")
      (node (ref "J7") (pin "P2") (pinfunction "2_P2") (pintype "passive"))
    )
    (net (code "135") (name "unconnected-(J8-2-PadP2)") (class "Default")
      (node (ref "J8") (pin "P2") (pinfunction "2_P2") (pintype "passive"))
    )
    (net (code "136") (name "unconnected-(J9-2-PadP2)") (class "Default")
      (node (ref "J9") (pin "P2") (pinfunction "2_P2") (pintype "passive"))
    )
    (net (code "137") (name "unconnected-(OK100-VE-Pad7)") (class "Default")
      (node (ref "OK100") (pin "7") (pinfunction "VE_7") (pintype "passive"))
    )
    (net (code "138") (name "unconnected-(U$1-1-PadP1)") (class "Default")
      (node (ref "U$1") (pin "P1") (pinfunction "1_P1") (pintype "passive"))
    )
  )
)
